# testcore.net
KiCad netlist of a schematic drawn in Altium Designer
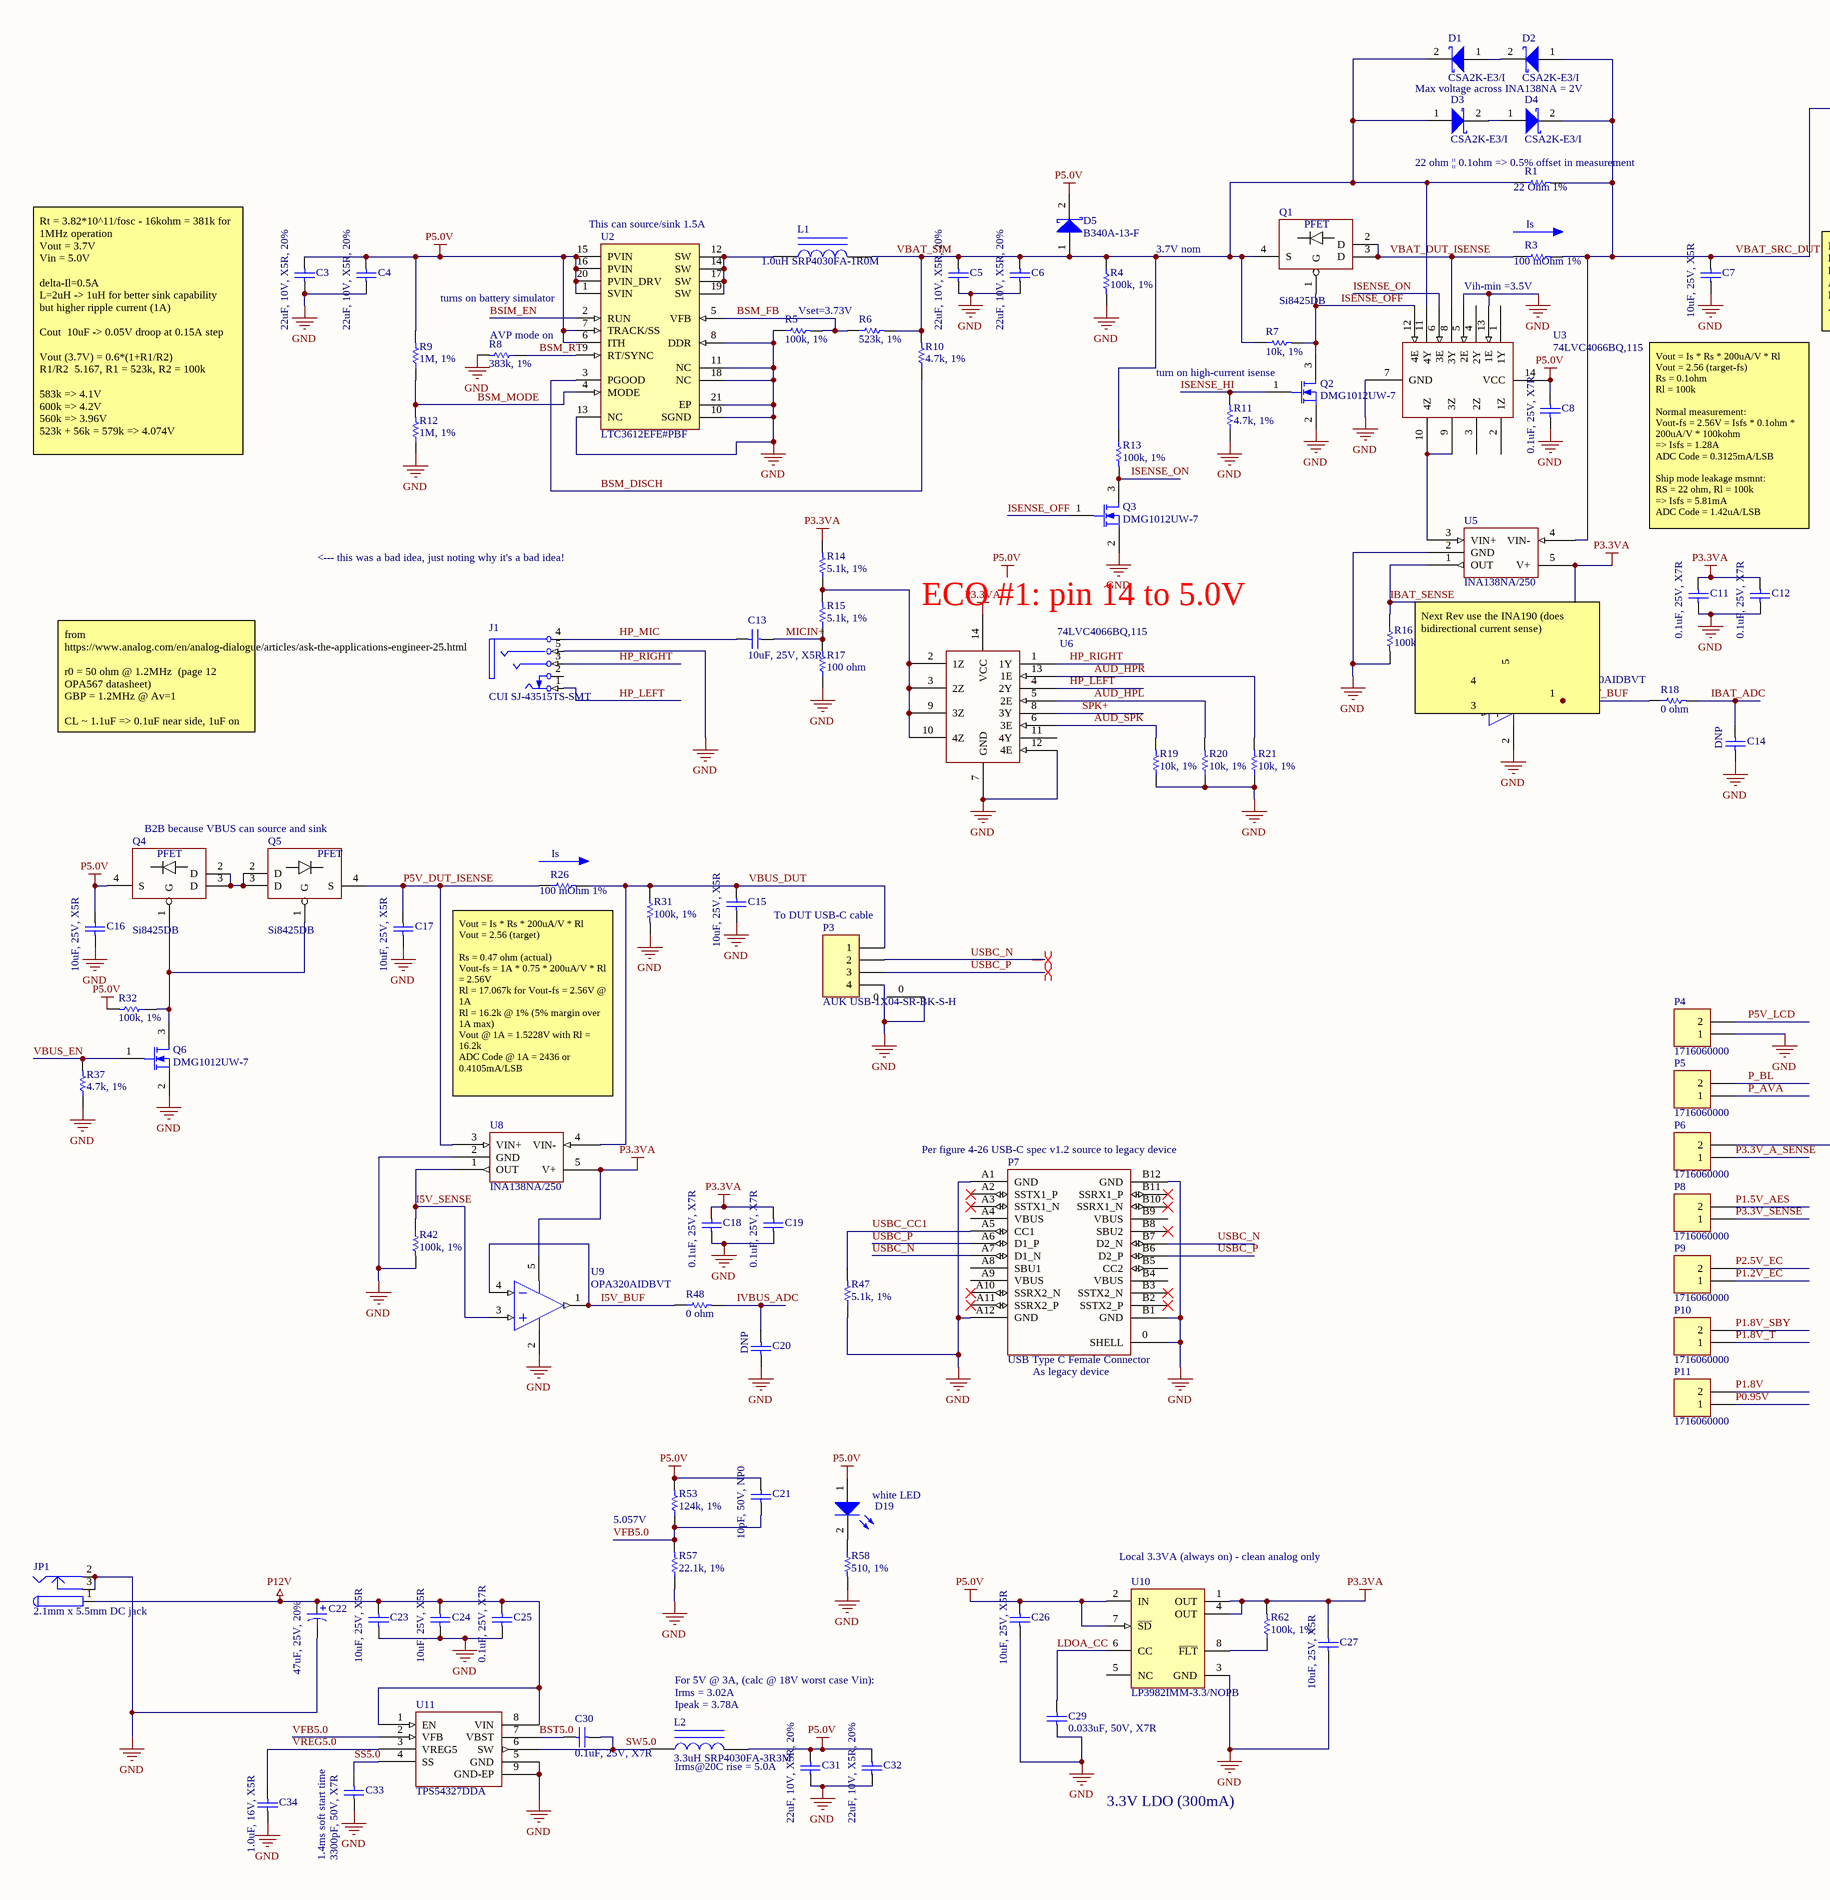
[diagram p0: testcore.SchDoc, left]
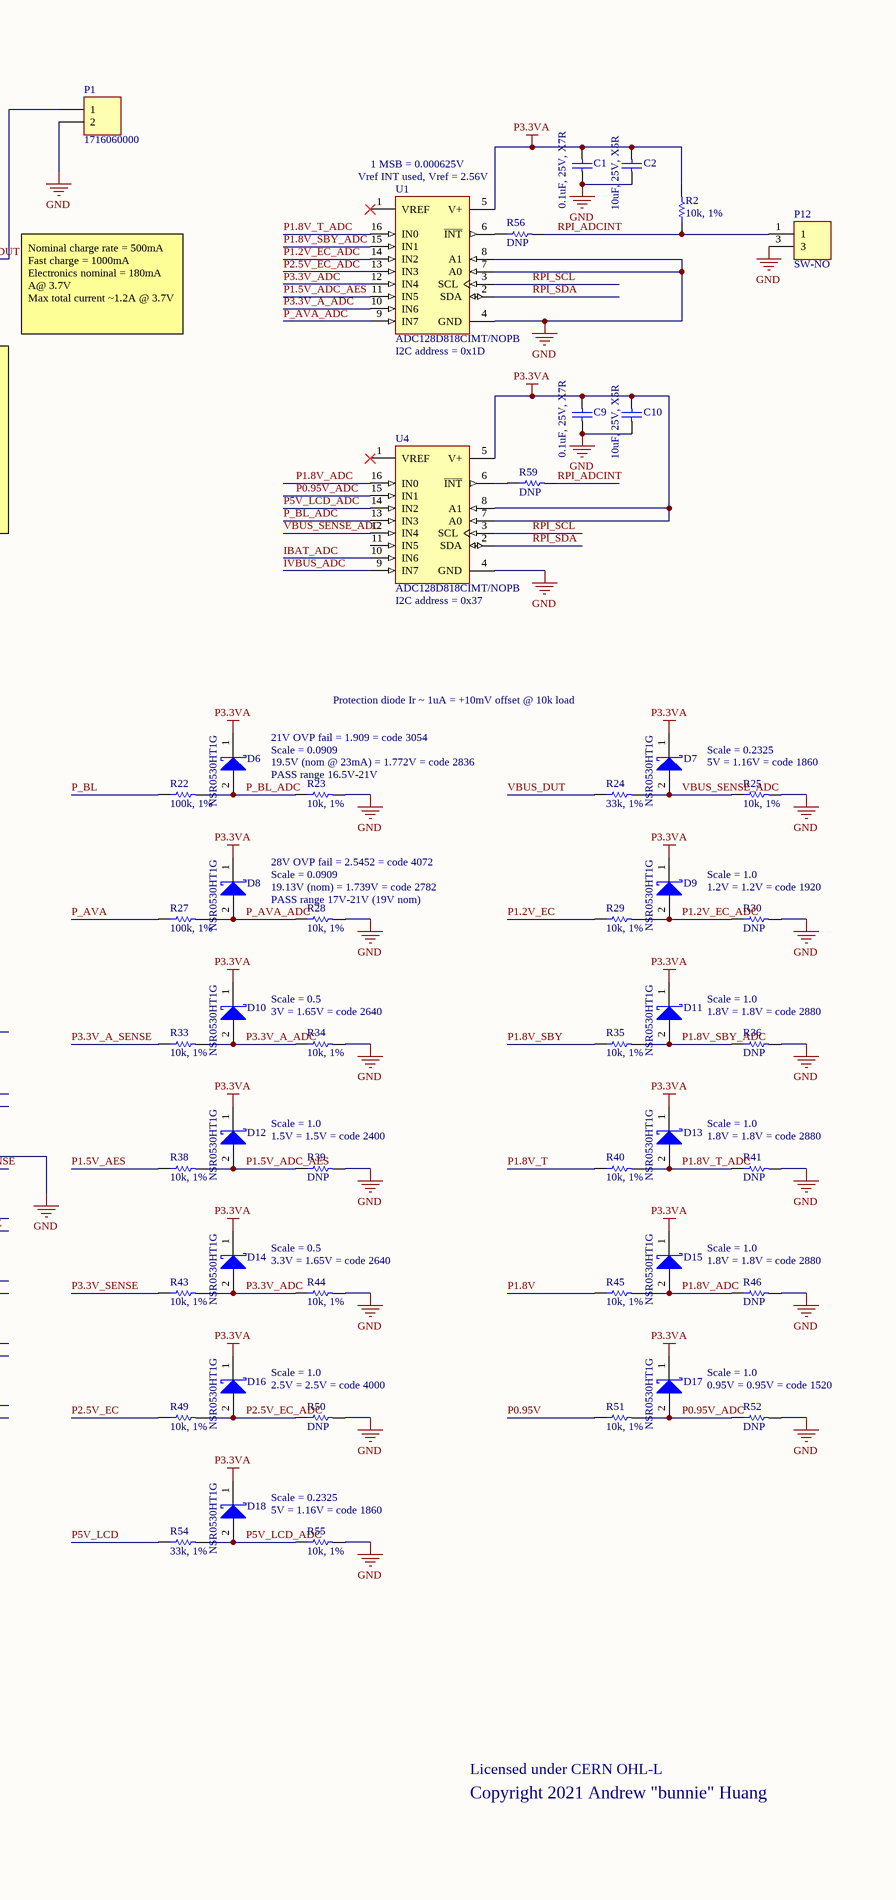
[diagram p1: testcore.SchDoc, right]

(export (version "E")
  (design (tool "Eeschema 10.0.6"))
  (components
    (comp (ref "C1")
      (value "0.1uF, 25V, X7R")
      (footprint "B_CAP0603")
      (description "Capacitor (Semiconductor SIM Model)")
      (fields (field (name "MPN") "CC0603KRX7R8BB104"))
      (libsource (lib "Miscellaneous Devices") (part "Cap Semi"))
    )
    (comp (ref "C2")
      (value "10uF, 25V, X5R")
      (footprint "B_CAP0805")
      (description "Capacitor (Semiconductor SIM Model)")
      (fields (field (name "MPN") "GRM21BR61E106KA73L"))
      (libsource (lib "Miscellaneous Devices") (part "Cap Semi"))
    )
    (comp (ref "C3")
      (value "22uF, 10V, X5R, 20%")
      (footprint "B_CAP0805")
      (description "Capacitor (Semiconductor SIM Model)")
      (fields
        (field (name "MFG") "Murata")
        (field (name "MPN") "GRM21BR61A226ME51L")
        (field (name "PUBLISHER") "Altium Limited")
      )
      (libsource (lib "Miscellaneous Devices") (part "Cap Semi"))
    )
    (comp (ref "C4")
      (value "22uF, 10V, X5R, 20%")
      (footprint "B_CAP0805")
      (description "Capacitor (Semiconductor SIM Model)")
      (fields
        (field (name "MFG") "Murata")
        (field (name "MPN") "GRM21BR61A226ME51L")
        (field (name "PUBLISHER") "Altium Limited")
      )
      (libsource (lib "Miscellaneous Devices") (part "Cap Semi"))
    )
    (comp (ref "C5")
      (value "22uF, 10V, X5R, 20%")
      (footprint "B_CAP0805")
      (description "Capacitor (Semiconductor SIM Model)")
      (fields
        (field (name "MFG") "Murata")
        (field (name "MPN") "GRM21BR61A226ME51L")
        (field (name "PUBLISHER") "Altium Limited")
      )
      (libsource (lib "Miscellaneous Devices") (part "Cap Semi"))
    )
    (comp (ref "C6")
      (value "22uF, 10V, X5R, 20%")
      (footprint "B_CAP0805")
      (description "Capacitor (Semiconductor SIM Model)")
      (fields
        (field (name "MFG") "Murata")
        (field (name "MPN") "GRM21BR61A226ME51L")
        (field (name "PUBLISHER") "Altium Limited")
      )
      (libsource (lib "Miscellaneous Devices") (part "Cap Semi"))
    )
    (comp (ref "C7")
      (value "10uF, 25V, X5R")
      (footprint "B_CAP0805")
      (description "Capacitor (Semiconductor SIM Model)")
      (fields (field (name "MPN") "GRM21BR61E106KA73L"))
      (libsource (lib "Miscellaneous Devices") (part "Cap Semi"))
    )
    (comp (ref "C8")
      (value "0.1uF, 25V, X7R")
      (footprint "B_CAP0603")
      (description "Capacitor (Semiconductor SIM Model)")
      (fields (field (name "MPN") "CC0603KRX7R8BB104"))
      (libsource (lib "Miscellaneous Devices") (part "Cap Semi"))
    )
    (comp (ref "C9")
      (value "0.1uF, 25V, X7R")
      (footprint "B_CAP0603")
      (description "Capacitor (Semiconductor SIM Model)")
      (fields (field (name "MPN") "CC0603KRX7R8BB104"))
      (libsource (lib "Miscellaneous Devices") (part "Cap Semi"))
    )
    (comp (ref "C10")
      (value "10uF, 25V, X5R")
      (footprint "B_CAP0805")
      (description "Capacitor (Semiconductor SIM Model)")
      (fields (field (name "MPN") "GRM21BR61E106KA73L"))
      (libsource (lib "Miscellaneous Devices") (part "Cap Semi"))
    )
    (comp (ref "C11")
      (value "0.1uF, 25V, X7R")
      (footprint "B_CAP0603")
      (description "Capacitor (Semiconductor SIM Model)")
      (fields (field (name "MPN") "CC0603KRX7R8BB104"))
      (libsource (lib "Miscellaneous Devices") (part "Cap Semi"))
    )
    (comp (ref "C12")
      (value "0.1uF, 25V, X7R")
      (footprint "B_CAP0603")
      (description "Capacitor (Semiconductor SIM Model)")
      (fields (field (name "MPN") "CC0603KRX7R8BB104"))
      (libsource (lib "Miscellaneous Devices") (part "Cap Semi"))
    )
    (comp (ref "C13")
      (value "10uF, 25V, X5R")
      (footprint "B_CAP0805")
      (description "Capacitor (Semiconductor SIM Model)")
      (fields (field (name "MPN") "GRM21BR61E106KA73L"))
      (libsource (lib "Miscellaneous Devices") (part "Cap Semi"))
    )
    (comp (ref "C14")
      (value "DNP")
      (footprint "B_CAP0603")
      (description "Capacitor (Semiconductor SIM Model)")
      (libsource (lib "Miscellaneous Devices") (part "Cap Semi"))
    )
    (comp (ref "C15")
      (value "10uF, 25V, X5R")
      (footprint "B_CAP0805")
      (description "Capacitor (Semiconductor SIM Model)")
      (fields (field (name "MPN") "GRM21BR61E106KA73L"))
      (libsource (lib "Miscellaneous Devices") (part "Cap Semi"))
    )
    (comp (ref "C16")
      (value "10uF, 25V, X5R")
      (footprint "B_CAP0805")
      (description "Capacitor (Semiconductor SIM Model)")
      (fields (field (name "MPN") "GRM21BR61E106KA73L"))
      (libsource (lib "Miscellaneous Devices") (part "Cap Semi"))
    )
    (comp (ref "C17")
      (value "10uF, 25V, X5R")
      (footprint "B_CAP0805")
      (description "Capacitor (Semiconductor SIM Model)")
      (fields (field (name "MPN") "GRM21BR61E106KA73L"))
      (libsource (lib "Miscellaneous Devices") (part "Cap Semi"))
    )
    (comp (ref "C18")
      (value "0.1uF, 25V, X7R")
      (footprint "B_CAP0603")
      (description "Capacitor (Semiconductor SIM Model)")
      (fields (field (name "MPN") "CC0603KRX7R8BB104"))
      (libsource (lib "Miscellaneous Devices") (part "Cap Semi"))
    )
    (comp (ref "C19")
      (value "0.1uF, 25V, X7R")
      (footprint "B_CAP0603")
      (description "Capacitor (Semiconductor SIM Model)")
      (fields (field (name "MPN") "CC0603KRX7R8BB104"))
      (libsource (lib "Miscellaneous Devices") (part "Cap Semi"))
    )
    (comp (ref "C20")
      (value "DNP")
      (footprint "B_CAP0603")
      (description "Capacitor (Semiconductor SIM Model)")
      (libsource (lib "Miscellaneous Devices") (part "Cap Semi"))
    )
    (comp (ref "C21")
      (value "10pF, 50V, NP0")
      (footprint "B_CAP0603")
      (description "Capacitor (Semiconductor SIM Model)")
      (fields (field (name "MPN") "CL10C100JB8NFNC"))
      (libsource (lib "Miscellaneous Devices") (part "Cap Semi"))
    )
    (comp (ref "C22")
      (value "47uF, 25V, 20%")
      (footprint "CAPAE7066X61N")
      (description "Polarized Capacitor (Radial)")
      (fields (field (name "MPN") "UCL1E470MCL1GS"))
      (libsource (lib "Miscellaneous Devices") (part "Cap Pol1"))
    )
    (comp (ref "C23")
      (value "10uF, 25V, X5R")
      (footprint "B_CAP0805")
      (description "Capacitor (Semiconductor SIM Model)")
      (fields (field (name "MPN") "GRM21BR61E106KA73L"))
      (libsource (lib "Miscellaneous Devices") (part "Cap Semi"))
    )
    (comp (ref "C24")
      (value "10uF, 25V, X5R")
      (footprint "B_CAP0805")
      (description "Capacitor (Semiconductor SIM Model)")
      (fields (field (name "MPN") "GRM21BR61E106KA73L"))
      (libsource (lib "Miscellaneous Devices") (part "Cap Semi"))
    )
    (comp (ref "C25")
      (value "0.1uF, 25V, X7R")
      (footprint "B_CAP0603")
      (description "Capacitor (Semiconductor SIM Model)")
      (fields (field (name "MPN") "CC0603KRX7R8BB104"))
      (libsource (lib "Miscellaneous Devices") (part "Cap Semi"))
    )
    (comp (ref "C26")
      (value "10uF, 25V, X5R")
      (footprint "B_CAP0805")
      (description "Capacitor (Semiconductor SIM Model)")
      (fields (field (name "MPN") "GRM21BR61E106KA73L"))
      (libsource (lib "Miscellaneous Devices") (part "Cap Semi"))
    )
    (comp (ref "C27")
      (value "10uF, 25V, X5R")
      (footprint "B_CAP0805")
      (description "Capacitor (Semiconductor SIM Model)")
      (fields (field (name "MPN") "GRM21BR61E106KA73L"))
      (libsource (lib "Miscellaneous Devices") (part "Cap Semi"))
    )
    (comp (ref "C29")
      (value "0.033uF, 50V, X7R")
      (footprint "B_CAP0603")
      (description "Capacitor (Semiconductor SIM Model)")
      (fields (field (name "MPN") "CL10B333KB8NNNC"))
      (libsource (lib "Miscellaneous Devices") (part "Cap Semi"))
    )
    (comp (ref "C30")
      (value "0.1uF, 25V, X7R")
      (footprint "B_CAP0603")
      (description "Capacitor (Semiconductor SIM Model)")
      (fields (field (name "MPN") "CC0603KRX7R8BB104"))
      (libsource (lib "Miscellaneous Devices") (part "Cap Semi"))
    )
    (comp (ref "C31")
      (value "22uF, 10V, X5R, 20%")
      (footprint "B_CAP0805")
      (description "Capacitor (Semiconductor SIM Model)")
      (fields
        (field (name "MFG") "Murata")
        (field (name "MPN") "GRM21BR61A226ME51L")
        (field (name "PUBLISHER") "Altium Limited")
      )
      (libsource (lib "Miscellaneous Devices") (part "Cap Semi"))
    )
    (comp (ref "C32")
      (value "22uF, 10V, X5R, 20%")
      (footprint "B_CAP0805")
      (description "Capacitor (Semiconductor SIM Model)")
      (fields
        (field (name "MFG") "Murata")
        (field (name "MPN") "GRM21BR61A226ME51L")
        (field (name "PUBLISHER") "Altium Limited")
      )
      (libsource (lib "Miscellaneous Devices") (part "Cap Semi"))
    )
    (comp (ref "C33")
      (value "3300pF, 50V, X7R")
      (footprint "B_CAP0603")
      (description "Capacitor (Semiconductor SIM Model)")
      (fields (field (name "MPN") "CL10B332KB8NNNC"))
      (libsource (lib "Miscellaneous Devices") (part "Cap Semi"))
    )
    (comp (ref "C34")
      (value "1.0uF, 16V, X5R")
      (footprint "B_CAP0603")
      (description "Capacitor (Semiconductor SIM Model)")
      (fields (field (name "MPN") "CL10B105MO8NNWC"))
      (libsource (lib "Miscellaneous Devices") (part "Cap Semi"))
    )
    (comp (ref "D1")
      (value "CSA2K-E3/I")
      (footprint "DSO-C2/X1.8")
      (description "Schottky Diode")
      (libsource (lib "") (part "D Schottky_1"))
    )
    (comp (ref "D2")
      (value "CSA2K-E3/I")
      (footprint "DSO-C2/X1.8")
      (description "Schottky Diode")
      (libsource (lib "") (part "D Schottky_1"))
    )
    (comp (ref "D3")
      (value "CSA2K-E3/I")
      (footprint "DSO-C2/X1.8")
      (description "Schottky Diode")
      (libsource (lib "") (part "D Schottky_1"))
    )
    (comp (ref "D4")
      (value "CSA2K-E3/I")
      (footprint "DSO-C2/X1.8")
      (description "Schottky Diode")
      (libsource (lib "") (part "D Schottky_1"))
    )
    (comp (ref "D5")
      (value "B340A-13-F")
      (footprint "DSO-C2/X1.8")
      (description "Schottky Diode")
      (libsource (lib "") (part "D Schottky_1"))
    )
    (comp (ref "D6")
      (value "NSR0530HT1G")
      (footprint "SOD-323")
      (description "Schottky Diode")
      (fields (field (name "MPN") "NSR0530H-D"))
      (libsource (lib "Miscellaneous Devices") (part "D Schottky"))
    )
    (comp (ref "D7")
      (value "NSR0530HT1G")
      (footprint "SOD-323")
      (description "Schottky Diode")
      (fields (field (name "MPN") "NSR0530H-D"))
      (libsource (lib "Miscellaneous Devices") (part "D Schottky"))
    )
    (comp (ref "D8")
      (value "NSR0530HT1G")
      (footprint "SOD-323")
      (description "Schottky Diode")
      (fields (field (name "MPN") "NSR0530H-D"))
      (libsource (lib "Miscellaneous Devices") (part "D Schottky"))
    )
    (comp (ref "D9")
      (value "NSR0530HT1G")
      (footprint "SOD-323")
      (description "Schottky Diode")
      (fields (field (name "MPN") "NSR0530H-D"))
      (libsource (lib "Miscellaneous Devices") (part "D Schottky"))
    )
    (comp (ref "D10")
      (value "NSR0530HT1G")
      (footprint "SOD-323")
      (description "Schottky Diode")
      (fields (field (name "MPN") "NSR0530H-D"))
      (libsource (lib "Miscellaneous Devices") (part "D Schottky"))
    )
    (comp (ref "D11")
      (value "NSR0530HT1G")
      (footprint "SOD-323")
      (description "Schottky Diode")
      (fields (field (name "MPN") "NSR0530H-D"))
      (libsource (lib "Miscellaneous Devices") (part "D Schottky"))
    )
    (comp (ref "D12")
      (value "NSR0530HT1G")
      (footprint "SOD-323")
      (description "Schottky Diode")
      (fields (field (name "MPN") "NSR0530H-D"))
      (libsource (lib "Miscellaneous Devices") (part "D Schottky"))
    )
    (comp (ref "D13")
      (value "NSR0530HT1G")
      (footprint "SOD-323")
      (description "Schottky Diode")
      (fields (field (name "MPN") "NSR0530H-D"))
      (libsource (lib "Miscellaneous Devices") (part "D Schottky"))
    )
    (comp (ref "D14")
      (value "NSR0530HT1G")
      (footprint "SOD-323")
      (description "Schottky Diode")
      (fields (field (name "MPN") "NSR0530H-D"))
      (libsource (lib "Miscellaneous Devices") (part "D Schottky"))
    )
    (comp (ref "D15")
      (value "NSR0530HT1G")
      (footprint "SOD-323")
      (description "Schottky Diode")
      (fields (field (name "MPN") "NSR0530H-D"))
      (libsource (lib "Miscellaneous Devices") (part "D Schottky"))
    )
    (comp (ref "D16")
      (value "NSR0530HT1G")
      (footprint "SOD-323")
      (description "Schottky Diode")
      (fields (field (name "MPN") "NSR0530H-D"))
      (libsource (lib "Miscellaneous Devices") (part "D Schottky"))
    )
    (comp (ref "D17")
      (value "NSR0530HT1G")
      (footprint "SOD-323")
      (description "Schottky Diode")
      (fields (field (name "MPN") "NSR0530H-D"))
      (libsource (lib "Miscellaneous Devices") (part "D Schottky"))
    )
    (comp (ref "D18")
      (value "NSR0530HT1G")
      (footprint "SOD-323")
      (description "Schottky Diode")
      (fields (field (name "MPN") "NSR0530H-D"))
      (libsource (lib "Miscellaneous Devices") (part "D Schottky"))
    )
    (comp (ref "D19")
      (value "white LED")
      (footprint "B_LED0805")
      (description "Typical RED, GREEN, YELLOW, AMBER GaAs LED")
      (fields (field (name "MPN") "IN-S85AT5UW"))
      (libsource (lib "Miscellaneous Devices") (part "LED2"))
    )
    (comp (ref "J1")
      (value "CUI SJ-43515TS-SMT")
      (footprint "CUI_SJ_43515TS-SMT")
      (description "Jack Socket, 3.5mm, SMT, 4-conductor")
      (fields (field (name "MPN") "SJ-43515TS-SMT") (field (name "PUBLISHER") "Altium Limited"))
      (libsource (lib "commonsch") (part "Phonejack4 TN"))
    )
    (comp (ref "JP1")
      (value "2.1mm x 5.5mm DC jack")
      (footprint "CUI_PJ_002AH_SMT")
      (description "Low Voltage Power Supply Connector")
      (fields (field (name "MPN") "DC-480-2.0A-SMT") (field (name "PUBLISHER") "Altium Limited"))
      (libsource (lib "Miscellaneous Connectors") (part "PWR2.5"))
    )
    (comp (ref "L1")
      (value "1.0uH SRP4030FA-1R0M")
      (footprint "COILCRAFT_XEL4030")
      (description "Magnetic-Core Inductor")
      (fields (field (name "MPN") "SRP4030FA-1R0M"))
      (libsource (lib "Miscellaneous Devices") (part "Inductor Iron"))
    )
    (comp (ref "L2")
      (value "3.3uH SRP4030FA-3R3M")
      (footprint "COILCRAFT_XEL4030")
      (description "Magnetic-Core Inductor")
      (fields (field (name "MPN") "XEL4030-332ME_"))
      (libsource (lib "Miscellaneous Devices") (part "Inductor Iron"))
    )
    (comp (ref "P1")
      (value "1716060000")
      (footprint "weidmuller_1716060000")
      (description "Header, 2-Pin")
      (fields (field (name "PUBLISHER") "Altium Limited"))
      (libsource (lib "") (part "Header 2_2"))
    )
    (comp (ref "P3")
      (value "AUK USB-1X04-SR-BK-S-H")
      (footprint "USB_TYPEA_TH_SINGLE")
      (description "Header, 4-Pin")
      (fields (field (name "PUBLISHER") "Altium Limited"))
      (libsource (lib "Miscellaneous Connectors") (part "Header 4"))
    )
    (comp (ref "P4")
      (value "1716060000")
      (footprint "weidmuller_1716060000")
      (description "Header, 2-Pin")
      (fields (field (name "PUBLISHER") "Altium Limited"))
      (libsource (lib "Miscellaneous Connectors") (part "Header 2"))
    )
    (comp (ref "P5")
      (value "1716060000")
      (footprint "weidmuller_1716060000")
      (description "Header, 2-Pin")
      (fields (field (name "PUBLISHER") "Altium Limited"))
      (libsource (lib "Miscellaneous Connectors") (part "Header 2"))
    )
    (comp (ref "P6")
      (value "1716060000")
      (footprint "weidmuller_1716060000")
      (description "Header, 2-Pin")
      (fields (field (name "PUBLISHER") "Altium Limited"))
      (libsource (lib "Miscellaneous Connectors") (part "Header 2"))
    )
    (comp (ref "P7")
      (value "USB Type C Female Connector")
      (footprint "HIROSE_CX90B1-24P")
      (description "USB Type C Connector")
      (fields (field (name "MPN") "1-2295018-2"))
      (libsource (lib "commonsch-new") (part "USB_TYPE_C"))
    )
    (comp (ref "P8")
      (value "1716060000")
      (footprint "weidmuller_1716060000")
      (description "Header, 2-Pin")
      (fields (field (name "PUBLISHER") "Altium Limited"))
      (libsource (lib "Miscellaneous Connectors") (part "Header 2"))
    )
    (comp (ref "P9")
      (value "1716060000")
      (footprint "weidmuller_1716060000")
      (description "Header, 2-Pin")
      (fields (field (name "PUBLISHER") "Altium Limited"))
      (libsource (lib "Miscellaneous Connectors") (part "Header 2"))
    )
    (comp (ref "P10")
      (value "1716060000")
      (footprint "weidmuller_1716060000")
      (description "Header, 2-Pin")
      (fields (field (name "PUBLISHER") "Altium Limited"))
      (libsource (lib "Miscellaneous Connectors") (part "Header 2"))
    )
    (comp (ref "P11")
      (value "1716060000")
      (footprint "weidmuller_1716060000")
      (description "Header, 2-Pin")
      (fields (field (name "PUBLISHER") "Altium Limited"))
      (libsource (lib "Miscellaneous Connectors") (part "Header 2"))
    )
    (comp (ref "P12")
      (value "SW-NO")
      (footprint "CK_KS11R22CQD")
      (description "Header, 2-Pin")
      (fields (field (name "PUBLISHER") "Altium Limited"))
      (libsource (lib "") (part "Header 2_1"))
    )
    (comp (ref "Q1")
      (value "Si8425DB")
      (footprint "VISHAY_MICRO_FOOT_4_BUMP")
      (description "P-channel 20V 6.2A 27mOhm @ -2.5V")
      (fields (field (name "MPN") "Si8425DB-T1-E1"))
      (libsource (lib "") (part "Si8425DB_1"))
    )
    (comp (ref "Q2")
      (value "DMG1012UW-7")
      (footprint "SOT323-3AN")
      (description "N-Channel MOSFET")
      (fields (field (name "PUBLISHER") "Altium Limited"))
      (libsource (lib "Miscellaneous Devices") (part "MOSFET-N"))
    )
    (comp (ref "Q3")
      (value "DMG1012UW-7")
      (footprint "SOT323-3AN")
      (description "N-Channel MOSFET")
      (fields (field (name "PUBLISHER") "Altium Limited"))
      (libsource (lib "Miscellaneous Devices") (part "MOSFET-N"))
    )
    (comp (ref "Q4")
      (value "Si8425DB")
      (footprint "VISHAY_MICRO_FOOT_4_BUMP")
      (description "P-channel 20V 6.2A 27mOhm @ -2.5V")
      (fields (field (name "MPN") "Si8425DB-T1-E1"))
      (libsource (lib "") (part "Si8425DB_1"))
    )
    (comp (ref "Q5")
      (value "Si8425DB")
      (footprint "VISHAY_MICRO_FOOT_4_BUMP")
      (description "P-channel 20V 6.2A 27mOhm @ -2.5V")
      (fields (field (name "MPN") "Si8425DB-T1-E1"))
      (libsource (lib "temp-to-merge") (part "Si8425DB"))
    )
    (comp (ref "Q6")
      (value "DMG1012UW-7")
      (footprint "SOT323-3AN")
      (description "N-Channel MOSFET")
      (fields (field (name "PUBLISHER") "Altium Limited"))
      (libsource (lib "Miscellaneous Devices") (part "MOSFET-N"))
    )
    (comp (ref "R1")
      (value "22 Ohm 1%")
      (footprint "B_RES1206")
      (description "Resistor")
      (fields (field (name "MPN") "ERJ-8ENF22R0V"))
      (libsource (lib "Miscellaneous Devices") (part "Res1"))
    )
    (comp (ref "R2")
      (value "10k, 1%")
      (footprint "B_RES0603")
      (description "Resistor")
      (fields (field (name "MPN") "RC0603FR-0710KL"))
      (libsource (lib "Miscellaneous Devices") (part "Res1"))
    )
    (comp (ref "R3")
      (value "100 mOhm 1%")
      (footprint "B_RES1206")
      (description "Resistor")
      (fields (field (name "MPN") "CSR1206FTR100"))
      (libsource (lib "Miscellaneous Devices") (part "Res1"))
    )
    (comp (ref "R4")
      (value "100k, 1%")
      (footprint "B_RES0603")
      (description "Resistor")
      (fields (field (name "MPN") "RC0603FR-07100KL"))
      (libsource (lib "Miscellaneous Devices") (part "Res1"))
    )
    (comp (ref "R5")
      (value "100k, 1%")
      (footprint "B_RES0603")
      (description "Resistor")
      (fields (field (name "MPN") "RC0603FR-07100KL"))
      (libsource (lib "Miscellaneous Devices") (part "Res1"))
    )
    (comp (ref "R6")
      (value "523k, 1%")
      (footprint "B_RES0603")
      (description "Resistor")
      (fields (field (name "MPN") "RC0603FR-07523KL"))
      (libsource (lib "Miscellaneous Devices") (part "Res1"))
    )
    (comp (ref "R7")
      (value "10k, 1%")
      (footprint "B_RES0603")
      (description "Resistor")
      (fields (field (name "MPN") "RC0603FR-0710KL"))
      (libsource (lib "Miscellaneous Devices") (part "Res1"))
    )
    (comp (ref "R8")
      (value "383k, 1%")
      (footprint "B_RES0603")
      (description "Resistor")
      (fields (field (name "MPN") "RC0603FR-07383KL"))
      (libsource (lib "Miscellaneous Devices") (part "Res1"))
    )
    (comp (ref "R9")
      (value "1M, 1%")
      (footprint "B_RES0603")
      (description "Resistor")
      (fields (field (name "MPN") "RC0603FR-071ML"))
      (libsource (lib "Miscellaneous Devices") (part "Res1"))
    )
    (comp (ref "R10")
      (value "4.7k, 1%")
      (footprint "B_RES0603")
      (description "Resistor")
      (fields (field (name "MPN") "RC0603FR-074K7L"))
      (libsource (lib "Miscellaneous Devices") (part "Res1"))
    )
    (comp (ref "R11")
      (value "4.7k, 1%")
      (footprint "B_RES0603")
      (description "Resistor")
      (fields (field (name "MPN") "RC0603FR-074K7L"))
      (libsource (lib "Miscellaneous Devices") (part "Res1"))
    )
    (comp (ref "R12")
      (value "1M, 1%")
      (footprint "B_RES0603")
      (description "Resistor")
      (fields (field (name "MPN") "RC0603FR-071ML"))
      (libsource (lib "Miscellaneous Devices") (part "Res1"))
    )
    (comp (ref "R13")
      (value "100k, 1%")
      (footprint "B_RES0603")
      (description "Resistor")
      (fields (field (name "MPN") "RC0603FR-07100KL"))
      (libsource (lib "Miscellaneous Devices") (part "Res1"))
    )
    (comp (ref "R14")
      (value "5.1k, 1%")
      (footprint "B_RES0603")
      (description "Resistor")
      (fields (field (name "MPN") "RC0603FR-075K1L"))
      (libsource (lib "Miscellaneous Devices") (part "Res1"))
    )
    (comp (ref "R15")
      (value "5.1k, 1%")
      (footprint "B_RES0603")
      (description "Resistor")
      (fields (field (name "MPN") "RC0603FR-075K1L"))
      (libsource (lib "Miscellaneous Devices") (part "Res1"))
    )
    (comp (ref "R16")
      (value "100k, 1%")
      (footprint "B_RES0603")
      (description "Resistor")
      (fields (field (name "MPN") "RC0603FR-07100KL"))
      (libsource (lib "Miscellaneous Devices") (part "Res1"))
    )
    (comp (ref "R17")
      (value "100 ohm")
      (footprint "B_RES0603")
      (description "Resistor")
      (fields (field (name "MPN") "RC0603FR-07100RL"))
      (libsource (lib "Miscellaneous Devices") (part "Res1"))
    )
    (comp (ref "R18")
      (value "0 ohm")
      (footprint "B_RES0603")
      (description "Resistor")
      (fields (field (name "MPN") "RC0603JR-070RL"))
      (libsource (lib "Miscellaneous Devices") (part "Res1"))
    )
    (comp (ref "R19")
      (value "10k, 1%")
      (footprint "B_RES0603")
      (description "Resistor")
      (fields (field (name "MPN") "RC0603FR-0710KL"))
      (libsource (lib "Miscellaneous Devices") (part "Res1"))
    )
    (comp (ref "R20")
      (value "10k, 1%")
      (footprint "B_RES0603")
      (description "Resistor")
      (fields (field (name "MPN") "RC0603FR-0710KL"))
      (libsource (lib "Miscellaneous Devices") (part "Res1"))
    )
    (comp (ref "R21")
      (value "10k, 1%")
      (footprint "B_RES0603")
      (description "Resistor")
      (fields (field (name "MPN") "RC0603FR-0710KL"))
      (libsource (lib "Miscellaneous Devices") (part "Res1"))
    )
    (comp (ref "R22")
      (value "100k, 1%")
      (footprint "B_RES0603")
      (description "Resistor")
      (fields (field (name "MPN") "RC0603FR-07100KL"))
      (libsource (lib "Miscellaneous Devices") (part "Res1"))
    )
    (comp (ref "R23")
      (value "10k, 1%")
      (footprint "B_RES0603")
      (description "Resistor")
      (fields (field (name "MPN") "RC0603FR-0710KL"))
      (libsource (lib "Miscellaneous Devices") (part "Res1"))
    )
    (comp (ref "R24")
      (value "33k, 1%")
      (footprint "B_RES0603")
      (description "Resistor")
      (fields (field (name "MPN") "RC0603FR-0733KL"))
      (libsource (lib "Miscellaneous Devices") (part "Res1"))
    )
    (comp (ref "R25")
      (value "10k, 1%")
      (footprint "B_RES0603")
      (description "Resistor")
      (fields (field (name "MPN") "RC0603FR-0710KL"))
      (libsource (lib "Miscellaneous Devices") (part "Res1"))
    )
    (comp (ref "R26")
      (value "100 mOhm 1%")
      (footprint "B_RES1206")
      (description "Resistor")
      (fields (field (name "MPN") "CSR1206FTR100"))
      (libsource (lib "Miscellaneous Devices") (part "Res1"))
    )
    (comp (ref "R27")
      (value "100k, 1%")
      (footprint "B_RES0603")
      (description "Resistor")
      (fields (field (name "MPN") "RC0603FR-07100KL"))
      (libsource (lib "Miscellaneous Devices") (part "Res1"))
    )
    (comp (ref "R28")
      (value "10k, 1%")
      (footprint "B_RES0603")
      (description "Resistor")
      (fields (field (name "MPN") "RC0603FR-0710KL"))
      (libsource (lib "Miscellaneous Devices") (part "Res1"))
    )
    (comp (ref "R29")
      (value "10k, 1%")
      (footprint "B_RES0603")
      (description "Resistor")
      (fields (field (name "MPN") "RC0603FR-0710KL"))
      (libsource (lib "Miscellaneous Devices") (part "Res1"))
    )
    (comp (ref "R30")
      (value "DNP")
      (footprint "B_RES0603")
      (description "Resistor")
      (fields (field (name "MPN") "ANY"))
      (libsource (lib "Miscellaneous Devices") (part "Res1"))
    )
    (comp (ref "R31")
      (value "100k, 1%")
      (footprint "B_RES0603")
      (description "Resistor")
      (fields (field (name "MPN") "RC0603FR-07100KL"))
      (libsource (lib "Miscellaneous Devices") (part "Res1"))
    )
    (comp (ref "R32")
      (value "100k, 1%")
      (footprint "B_RES0603")
      (description "Resistor")
      (fields (field (name "MPN") "RC0603FR-07100KL"))
      (libsource (lib "Miscellaneous Devices") (part "Res1"))
    )
    (comp (ref "R33")
      (value "10k, 1%")
      (footprint "B_RES0603")
      (description "Resistor")
      (fields (field (name "MPN") "RC0603FR-0710KL"))
      (libsource (lib "Miscellaneous Devices") (part "Res1"))
    )
    (comp (ref "R34")
      (value "10k, 1%")
      (footprint "B_RES0603")
      (description "Resistor")
      (fields (field (name "MPN") "RC0603FR-0710KL"))
      (libsource (lib "Miscellaneous Devices") (part "Res1"))
    )
    (comp (ref "R35")
      (value "10k, 1%")
      (footprint "B_RES0603")
      (description "Resistor")
      (fields (field (name "MPN") "RC0603FR-0710KL"))
      (libsource (lib "Miscellaneous Devices") (part "Res1"))
    )
    (comp (ref "R36")
      (value "DNP")
      (footprint "B_RES0603")
      (description "Resistor")
      (fields (field (name "MPN") "ANY"))
      (libsource (lib "Miscellaneous Devices") (part "Res1"))
    )
    (comp (ref "R37")
      (value "4.7k, 1%")
      (footprint "B_RES0603")
      (description "Resistor")
      (fields (field (name "MPN") "RC0603FR-074K7L"))
      (libsource (lib "Miscellaneous Devices") (part "Res1"))
    )
    (comp (ref "R38")
      (value "10k, 1%")
      (footprint "B_RES0603")
      (description "Resistor")
      (fields (field (name "MPN") "RC0603FR-0710KL"))
      (libsource (lib "Miscellaneous Devices") (part "Res1"))
    )
    (comp (ref "R39")
      (value "DNP")
      (footprint "B_RES0603")
      (description "Resistor")
      (fields (field (name "MPN") "ANY"))
      (libsource (lib "Miscellaneous Devices") (part "Res1"))
    )
    (comp (ref "R40")
      (value "10k, 1%")
      (footprint "B_RES0603")
      (description "Resistor")
      (fields (field (name "MPN") "RC0603FR-0710KL"))
      (libsource (lib "Miscellaneous Devices") (part "Res1"))
    )
    (comp (ref "R41")
      (value "DNP")
      (footprint "B_RES0603")
      (description "Resistor")
      (fields (field (name "MPN") "ANY"))
      (libsource (lib "Miscellaneous Devices") (part "Res1"))
    )
    (comp (ref "R42")
      (value "100k, 1%")
      (footprint "B_RES0603")
      (description "Resistor")
      (fields (field (name "MPN") "RC0603FR-07100KL"))
      (libsource (lib "Miscellaneous Devices") (part "Res1"))
    )
    (comp (ref "R43")
      (value "10k, 1%")
      (footprint "B_RES0603")
      (description "Resistor")
      (fields (field (name "MPN") "RC0603FR-0710KL"))
      (libsource (lib "Miscellaneous Devices") (part "Res1"))
    )
    (comp (ref "R44")
      (value "10k, 1%")
      (footprint "B_RES0603")
      (description "Resistor")
      (fields (field (name "MPN") "RC0603FR-0710KL"))
      (libsource (lib "Miscellaneous Devices") (part "Res1"))
    )
    (comp (ref "R45")
      (value "10k, 1%")
      (footprint "B_RES0603")
      (description "Resistor")
      (fields (field (name "MPN") "RC0603FR-0710KL"))
      (libsource (lib "Miscellaneous Devices") (part "Res1"))
    )
    (comp (ref "R46")
      (value "DNP")
      (footprint "B_RES0603")
      (description "Resistor")
      (fields (field (name "MPN") "ANY"))
      (libsource (lib "Miscellaneous Devices") (part "Res1"))
    )
    (comp (ref "R47")
      (value "5.1k, 1%")
      (footprint "B_RES0603")
      (description "Resistor")
      (fields (field (name "MPN") "RC0603FR-075K1L"))
      (libsource (lib "Miscellaneous Devices") (part "Res1"))
    )
    (comp (ref "R48")
      (value "0 ohm")
      (footprint "B_RES0603")
      (description "Resistor")
      (fields (field (name "MPN") "RC0603JR-070RL"))
      (libsource (lib "Miscellaneous Devices") (part "Res1"))
    )
    (comp (ref "R49")
      (value "10k, 1%")
      (footprint "B_RES0603")
      (description "Resistor")
      (fields (field (name "MPN") "RC0603FR-0710KL"))
      (libsource (lib "Miscellaneous Devices") (part "Res1"))
    )
    (comp (ref "R50")
      (value "DNP")
      (footprint "B_RES0603")
      (description "Resistor")
      (fields (field (name "MPN") "ANY"))
      (libsource (lib "Miscellaneous Devices") (part "Res1"))
    )
    (comp (ref "R51")
      (value "10k, 1%")
      (footprint "B_RES0603")
      (description "Resistor")
      (fields (field (name "MPN") "RC0603FR-0710KL"))
      (libsource (lib "Miscellaneous Devices") (part "Res1"))
    )
    (comp (ref "R52")
      (value "DNP")
      (footprint "B_RES0603")
      (description "Resistor")
      (fields (field (name "MPN") "ANY"))
      (libsource (lib "Miscellaneous Devices") (part "Res1"))
    )
    (comp (ref "R53")
      (value "124k, 1%")
      (footprint "B_RES0603")
      (description "Resistor")
      (fields (field (name "MPN") "RC0603FR-07124KL"))
      (libsource (lib "Miscellaneous Devices") (part "Res1"))
    )
    (comp (ref "R54")
      (value "33k, 1%")
      (footprint "B_RES0603")
      (description "Resistor")
      (fields (field (name "MPN") "RC0603FR-0733KL"))
      (libsource (lib "Miscellaneous Devices") (part "Res1"))
    )
    (comp (ref "R55")
      (value "10k, 1%")
      (footprint "B_RES0603")
      (description "Resistor")
      (fields (field (name "MPN") "RC0603FR-0710KL"))
      (libsource (lib "Miscellaneous Devices") (part "Res1"))
    )
    (comp (ref "R56")
      (value "DNP")
      (footprint "B_RES0603")
      (description "Resistor")
      (fields (field (name "MPN") "ANY"))
      (libsource (lib "Miscellaneous Devices") (part "Res1"))
    )
    (comp (ref "R57")
      (value "22.1k, 1%")
      (footprint "B_RES0603")
      (description "Resistor")
      (fields (field (name "MPN") "RC0603FR-0722K1L"))
      (libsource (lib "Miscellaneous Devices") (part "Res1"))
    )
    (comp (ref "R58")
      (value "510, 1%")
      (footprint "B_RES0603")
      (description "Resistor")
      (fields (field (name "MPN") "RC0603FR-07510RL") (field (name "PUBLISHER") "Altium Limited"))
      (libsource (lib "Miscellaneous Devices") (part "Res1"))
    )
    (comp (ref "R59")
      (value "DNP")
      (footprint "B_RES0603")
      (description "Resistor")
      (fields (field (name "MPN") "ANY"))
      (libsource (lib "Miscellaneous Devices") (part "Res1"))
    )
    (comp (ref "R62")
      (value "100k, 1%")
      (footprint "B_RES0603")
      (description "Resistor")
      (fields (field (name "MPN") "RC0603FR-07100KL"))
      (libsource (lib "Miscellaneous Devices") (part "Res1"))
    )
    (comp (ref "U1")
      (value "ADC128D818CIMT/NOPB")
      (footprint "MTC16_N")
      (fields (field (name "MANUFACTURER") "National Semiconductor"))
      (libsource (lib "National Semiconductor ADC") (part "ADC128D818CIMT/NOPB"))
    )
    (comp (ref "U2")
      (value "LTC3612EFE#PBF")
      (footprint "LT-FE-20-EPV-CB_L")
      (libsource (lib "Altium Content Vault") (part "LT-LTC3612-FE-20"))
    )
    (comp (ref "U3")
      (value "74LVC4066BQ,115")
      (footprint "NXP_DHVQFN14")
      (description "Quad Bilateral Switch")
      (libsource (lib "commonsch-new") (part "74LVC4066"))
    )
    (comp (ref "U4")
      (value "ADC128D818CIMT/NOPB")
      (footprint "MTC16_N")
      (fields (field (name "MANUFACTURER") "National Semiconductor"))
      (libsource (lib "National Semiconductor ADC") (part "ADC128D818CIMT/NOPB"))
    )
    (comp (ref "U5")
      (value "INA138NA/250")
      (footprint "SOT23-5AN")
      (description "High-side measurement current shunt monitor")
      (libsource (lib "commonsch-new") (part "INA138NA/250"))
    )
    (comp (ref "U6")
      (value "74LVC4066BQ,115")
      (footprint "NXP_DHVQFN14")
      (description "Quad Bilateral Switch")
      (libsource (lib "commonsch-new") (part "74LVC4066"))
    )
    (comp (ref "U7")
      (value "OPA320AIDBVT")
      (footprint "TI-DBV5_N")
      (fields (field (name "MANUFACTURER") "Texas Instruments"))
      (libsource (lib "TI Amplifiers and Linear Operational Amplifier Precision Amplifier Part One") (part "OPA320AIDBVT"))
    )
    (comp (ref "U8")
      (value "INA138NA/250")
      (footprint "SOT23-5AN")
      (description "High-side measurement current shunt monitor")
      (libsource (lib "commonsch-new") (part "INA138NA/250"))
    )
    (comp (ref "U9")
      (value "OPA320AIDBVT")
      (footprint "TI-DBV5_N")
      (fields (field (name "MANUFACTURER") "Texas Instruments"))
      (libsource (lib "TI Amplifiers and Linear Operational Amplifier Precision Amplifier Part One") (part "OPA320AIDBVT"))
    )
    (comp (ref "U10")
      (value "LP3982IMM-3.3/NOPB")
      (footprint "MUA08A_N")
      (description "Micropower, Ultra Low-Dropout, Low-Noise, 300mA CMOS Regulator, 8-pin Mini SOIC, Pb-Free")
      (fields (field (name "MANUFACTURER") "National Semiconductor"))
      (libsource (lib "National Semiconductor LDO") (part "LP3982IMM-3.3/NOPB"))
    )
    (comp (ref "U11")
      (value "TPS54327DDA")
      (footprint "SOIC127P600-8DN")
      (description "3-A Output Single Synchronous Step-Down Buck with Integrated FET")
      (fields (field (name "MPN") "TPS54327DDA(R)"))
      (libsource (lib "commonsch-new") (part "TPS54327DDA"))
    )
  )
  (nets
    (net (code "1") (name "/AUD_HPL") (class "Default")
      (node (ref "R20") (pin "2") (pinfunction "2_2") (pintype "passive"))
      (node (ref "U6") (pin "5") (pinfunction "2E_5") (pintype "input"))
    )
    (net (code "2") (name "/AUD_HPR") (class "Default")
      (node (ref "R21") (pin "2") (pinfunction "2_2") (pintype "passive"))
      (node (ref "U6") (pin "13") (pinfunction "1E_13") (pintype "input"))
    )
    (net (code "3") (name "/AUD_SPK") (class "Default")
      (node (ref "R19") (pin "2") (pinfunction "2_2") (pintype "passive"))
      (node (ref "U6") (pin "6") (pinfunction "3E_6") (pintype "input"))
    )
    (net (code "4") (name "/BSIM_EN") (class "Default")
      (node (ref "U2") (pin "2") (pinfunction "RUN_2") (pintype "input"))
    )
    (net (code "5") (name "/BSM_DISCH") (class "Default")
      (node (ref "R10") (pin "1") (pinfunction "1_1") (pintype "passive"))
      (node (ref "U2") (pin "3") (pinfunction "PGOOD_3") (pintype "open_collector"))
    )
    (net (code "6") (name "/BSM_FB") (class "Default")
      (node (ref "R5") (pin "2") (pinfunction "2_2") (pintype "passive"))
      (node (ref "R6") (pin "1") (pinfunction "1_1") (pintype "passive"))
      (node (ref "U2") (pin "5") (pinfunction "VFB_5") (pintype "input"))
    )
    (net (code "7") (name "/BSM_MODE") (class "Default")
      (node (ref "R12") (pin "2") (pinfunction "2_2") (pintype "passive"))
      (node (ref "R9") (pin "1") (pinfunction "1_1") (pintype "passive"))
      (node (ref "U2") (pin "4") (pinfunction "MODE_4") (pintype "input"))
    )
    (net (code "8") (name "/BSM_RT") (class "Default")
      (node (ref "R8") (pin "1") (pinfunction "1_1") (pintype "passive"))
      (node (ref "U2") (pin "9") (pinfunction "RT/SYNC_9") (pintype "input"))
    )
    (net (code "9") (name "/BST5.0") (class "Default")
      (node (ref "C30") (pin "2") (pinfunction "2_2") (pintype "passive"))
      (node (ref "U11") (pin "7") (pinfunction "VBST_7") (pintype "passive"))
    )
    (net (code "10") (name "/HP_LEFT") (class "Default")
      (node (ref "J1") (pin "1") (pinfunction "T_1") (pintype "input"))
      (node (ref "U6") (pin "4") (pinfunction "2Y_4") (pintype "passive"))
    )
    (net (code "11") (name "/HP_MIC") (class "Default")
      (node (ref "C13") (pin "2") (pinfunction "2_2") (pintype "passive"))
      (node (ref "J1") (pin "4") (pinfunction "S_4") (pintype "power_in"))
    )
    (net (code "12") (name "/HP_RIGHT") (class "Default")
      (node (ref "J1") (pin "3") (pinfunction "R_3") (pintype "input"))
      (node (ref "U6") (pin "1") (pinfunction "1Y_1") (pintype "passive"))
    )
    (net (code "13") (name "/I5V_BUF") (class "Default")
      (node (ref "R48") (pin "1") (pinfunction "1_1") (pintype "passive"))
      (node (ref "U9") (pin "1") (pinfunction "OUT_1") (pintype "output"))
      (node (ref "U9") (pin "4") (pinfunction "IN-_4") (pintype "input"))
    )
    (net (code "14") (name "/I5V_SENSE") (class "Default")
      (node (ref "R42") (pin "1") (pinfunction "1_1") (pintype "passive"))
      (node (ref "U8") (pin "1") (pinfunction "OUT_1") (pintype "output"))
      (node (ref "U9") (pin "3") (pinfunction "IN+_3") (pintype "input"))
    )
    (net (code "15") (name "/IBAT_ADC") (class "Default")
      (node (ref "C14") (pin "1") (pinfunction "1_1") (pintype "passive"))
      (node (ref "R18") (pin "2") (pinfunction "2_2") (pintype "passive"))
      (node (ref "U4") (pin "10") (pinfunction "IN6_10") (pintype "input"))
    )
    (net (code "16") (name "/IBAT_BUF") (class "Default")
      (node (ref "R18") (pin "1") (pinfunction "1_1") (pintype "passive"))
      (node (ref "U7") (pin "1") (pinfunction "OUT_1") (pintype "output"))
      (node (ref "U7") (pin "4") (pinfunction "IN-_4") (pintype "input"))
    )
    (net (code "17") (name "/IBAT_SENSE") (class "Default")
      (node (ref "R16") (pin "1") (pinfunction "1_1") (pintype "passive"))
      (node (ref "U5") (pin "1") (pinfunction "OUT_1") (pintype "output"))
      (node (ref "U7") (pin "3") (pinfunction "IN+_3") (pintype "input"))
    )
    (net (code "18") (name "/ISENSE_HI") (class "Default")
      (node (ref "Q2") (pin "1") (pinfunction "G_1") (pintype "passive"))
      (node (ref "R11") (pin "2") (pinfunction "2_2") (pintype "passive"))
    )
    (net (code "19") (name "/ISENSE_OFF") (class "Default")
      (node (ref "Q1") (pin "1") (pinfunction "G_1") (pintype "passive"))
      (node (ref "Q2") (pin "3") (pinfunction "D_3") (pintype "passive"))
      (node (ref "Q3") (pin "1") (pinfunction "G_1") (pintype "passive"))
      (node (ref "R7") (pin "2") (pinfunction "2_2") (pintype "passive"))
      (node (ref "U3") (pin "12") (pinfunction "4E_12") (pintype "input"))
    )
    (net (code "20") (name "/ISENSE_ON") (class "Default")
      (node (ref "Q3") (pin "3") (pinfunction "D_3") (pintype "passive"))
      (node (ref "R13") (pin "2") (pinfunction "2_2") (pintype "passive"))
      (node (ref "U3") (pin "6") (pinfunction "3E_6") (pintype "input"))
    )
    (net (code "21") (name "/IVBUS_ADC") (class "Default")
      (node (ref "C20") (pin "1") (pinfunction "1_1") (pintype "passive"))
      (node (ref "R48") (pin "2") (pinfunction "2_2") (pintype "passive"))
      (node (ref "U4") (pin "9") (pinfunction "IN7_9") (pintype "input"))
    )
    (net (code "22") (name "/LDOA_CC") (class "Default")
      (node (ref "C29") (pin "2") (pinfunction "2_2") (pintype "passive"))
      (node (ref "U10") (pin "6") (pinfunction "CC_6") (pintype "passive"))
    )
    (net (code "23") (name "/MICIN+") (class "Default")
      (node (ref "C13") (pin "1") (pinfunction "1_1") (pintype "passive"))
      (node (ref "R15") (pin "1") (pinfunction "1_1") (pintype "passive"))
      (node (ref "R17") (pin "2") (pinfunction "2_2") (pintype "passive"))
    )
    (net (code "24") (name "/P0.95V") (class "Default")
      (node (ref "P11") (pin "1") (pinfunction "1_1") (pintype "passive"))
      (node (ref "R51") (pin "1") (pinfunction "1_1") (pintype "passive"))
    )
    (net (code "25") (name "/P0.95V_ADC") (class "Default")
      (node (ref "D17") (pin "2") (pinfunction "A_2") (pintype "passive"))
      (node (ref "R51") (pin "2") (pinfunction "2_2") (pintype "passive"))
      (node (ref "R52") (pin "1") (pinfunction "1_1") (pintype "passive"))
      (node (ref "U4") (pin "15") (pinfunction "IN1_15") (pintype "input"))
    )
    (net (code "26") (name "/P1.2V_EC") (class "Default")
      (node (ref "P9") (pin "1") (pinfunction "1_1") (pintype "passive"))
      (node (ref "R29") (pin "1") (pinfunction "1_1") (pintype "passive"))
    )
    (net (code "27") (name "/P1.2V_EC_ADC") (class "Default")
      (node (ref "D9") (pin "2") (pinfunction "A_2") (pintype "passive"))
      (node (ref "R29") (pin "2") (pinfunction "2_2") (pintype "passive"))
      (node (ref "R30") (pin "1") (pinfunction "1_1") (pintype "passive"))
      (node (ref "U1") (pin "14") (pinfunction "IN2_14") (pintype "input"))
    )
    (net (code "28") (name "/P1.5V_ADC_AES") (class "Default")
      (node (ref "D12") (pin "2") (pinfunction "A_2") (pintype "passive"))
      (node (ref "R38") (pin "2") (pinfunction "2_2") (pintype "passive"))
      (node (ref "R39") (pin "1") (pinfunction "1_1") (pintype "passive"))
      (node (ref "U1") (pin "11") (pinfunction "IN5_11") (pintype "input"))
    )
    (net (code "29") (name "/P1.5V_AES") (class "Default")
      (node (ref "P8") (pin "2") (pinfunction "2_2") (pintype "passive"))
      (node (ref "R38") (pin "1") (pinfunction "1_1") (pintype "passive"))
    )
    (net (code "30") (name "/P1.8V") (class "Default")
      (node (ref "P11") (pin "2") (pinfunction "2_2") (pintype "passive"))
      (node (ref "R45") (pin "1") (pinfunction "1_1") (pintype "passive"))
    )
    (net (code "31") (name "/P1.8V_ADC") (class "Default")
      (node (ref "D15") (pin "2") (pinfunction "A_2") (pintype "passive"))
      (node (ref "R45") (pin "2") (pinfunction "2_2") (pintype "passive"))
      (node (ref "R46") (pin "1") (pinfunction "1_1") (pintype "passive"))
      (node (ref "U4") (pin "16") (pinfunction "IN0_16") (pintype "input"))
    )
    (net (code "32") (name "/P1.8V_SBY") (class "Default")
      (node (ref "P10") (pin "2") (pinfunction "2_2") (pintype "passive"))
      (node (ref "R35") (pin "1") (pinfunction "1_1") (pintype "passive"))
    )
    (net (code "33") (name "/P1.8V_SBY_ADC") (class "Default")
      (node (ref "D11") (pin "2") (pinfunction "A_2") (pintype "passive"))
      (node (ref "R35") (pin "2") (pinfunction "2_2") (pintype "passive"))
      (node (ref "R36") (pin "1") (pinfunction "1_1") (pintype "passive"))
      (node (ref "U1") (pin "15") (pinfunction "IN1_15") (pintype "input"))
    )
    (net (code "34") (name "/P1.8V_T") (class "Default")
      (node (ref "P10") (pin "1") (pinfunction "1_1") (pintype "passive"))
      (node (ref "R40") (pin "1") (pinfunction "1_1") (pintype "passive"))
    )
    (net (code "35") (name "/P1.8V_T_ADC") (class "Default")
      (node (ref "D13") (pin "2") (pinfunction "A_2") (pintype "passive"))
      (node (ref "R40") (pin "2") (pinfunction "2_2") (pintype "passive"))
      (node (ref "R41") (pin "1") (pinfunction "1_1") (pintype "passive"))
      (node (ref "U1") (pin "16") (pinfunction "IN0_16") (pintype "input"))
    )
    (net (code "36") (name "/P2.5V_EC") (class "Default")
      (node (ref "P9") (pin "2") (pinfunction "2_2") (pintype "passive"))
      (node (ref "R49") (pin "1") (pinfunction "1_1") (pintype "passive"))
    )
    (net (code "37") (name "/P2.5V_EC_ADC") (class "Default")
      (node (ref "D16") (pin "2") (pinfunction "A_2") (pintype "passive"))
      (node (ref "R49") (pin "2") (pinfunction "2_2") (pintype "passive"))
      (node (ref "R50") (pin "1") (pinfunction "1_1") (pintype "passive"))
      (node (ref "U1") (pin "13") (pinfunction "IN3_13") (pintype "input"))
    )
    (net (code "38") (name "/P3.3V_ADC") (class "Default")
      (node (ref "D14") (pin "2") (pinfunction "A_2") (pintype "passive"))
      (node (ref "R43") (pin "2") (pinfunction "2_2") (pintype "passive"))
      (node (ref "R44") (pin "1") (pinfunction "1_1") (pintype "passive"))
      (node (ref "U1") (pin "12") (pinfunction "IN4_12") (pintype "input"))
    )
    (net (code "39") (name "/P3.3V_A_ADC") (class "Default")
      (node (ref "D10") (pin "2") (pinfunction "A_2") (pintype "passive"))
      (node (ref "R33") (pin "2") (pinfunction "2_2") (pintype "passive"))
      (node (ref "R34") (pin "1") (pinfunction "1_1") (pintype "passive"))
      (node (ref "U1") (pin "10") (pinfunction "IN6_10") (pintype "input"))
    )
    (net (code "40") (name "/P3.3V_A_SENSE") (class "Default")
      (node (ref "P6") (pin "1") (pinfunction "1_1") (pintype "passive"))
      (node (ref "R33") (pin "1") (pinfunction "1_1") (pintype "passive"))
    )
    (net (code "41") (name "/P3.3V_SENSE") (class "Default")
      (node (ref "P8") (pin "1") (pinfunction "1_1") (pintype "passive"))
      (node (ref "R43") (pin "1") (pinfunction "1_1") (pintype "passive"))
    )
    (net (code "42") (name "/P5V_DUT_ISENSE") (class "Default")
      (node (ref "C17") (pin "2") (pinfunction "2_2") (pintype "passive"))
      (node (ref "Q5") (pin "4") (pinfunction "S_4") (pintype "passive"))
      (node (ref "R26") (pin "1") (pinfunction "1_1") (pintype "passive"))
      (node (ref "U8") (pin "3") (pinfunction "VIN+_3") (pintype "input"))
    )
    (net (code "43") (name "/P5V_LCD") (class "Default")
      (node (ref "P4") (pin "2") (pinfunction "2_2") (pintype "passive"))
      (node (ref "R54") (pin "1") (pinfunction "1_1") (pintype "passive"))
    )
    (net (code "44") (name "/P5V_LCD_ADC") (class "Default")
      (node (ref "D18") (pin "2") (pinfunction "A_2") (pintype "passive"))
      (node (ref "R54") (pin "2") (pinfunction "2_2") (pintype "passive"))
      (node (ref "R55") (pin "1") (pinfunction "1_1") (pintype "passive"))
      (node (ref "U4") (pin "14") (pinfunction "IN2_14") (pintype "input"))
    )
    (net (code "45") (name "/P_AVA") (class "Default")
      (node (ref "P5") (pin "1") (pinfunction "1_1") (pintype "passive"))
      (node (ref "R27") (pin "1") (pinfunction "1_1") (pintype "passive"))
    )
    (net (code "46") (name "/P_AVA_ADC") (class "Default")
      (node (ref "D8") (pin "2") (pinfunction "A_2") (pintype "passive"))
      (node (ref "R27") (pin "2") (pinfunction "2_2") (pintype "passive"))
      (node (ref "R28") (pin "1") (pinfunction "1_1") (pintype "passive"))
      (node (ref "U1") (pin "9") (pinfunction "IN7_9") (pintype "input"))
    )
    (net (code "47") (name "/P_BL") (class "Default")
      (node (ref "P5") (pin "2") (pinfunction "2_2") (pintype "passive"))
      (node (ref "R22") (pin "1") (pinfunction "1_1") (pintype "passive"))
    )
    (net (code "48") (name "/P_BL_ADC") (class "Default")
      (node (ref "D6") (pin "2") (pinfunction "A_2") (pintype "passive"))
      (node (ref "R22") (pin "2") (pinfunction "2_2") (pintype "passive"))
      (node (ref "R23") (pin "1") (pinfunction "1_1") (pintype "passive"))
      (node (ref "U4") (pin "13") (pinfunction "IN3_13") (pintype "input"))
    )
    (net (code "49") (name "/RPI_ADCINT") (class "Default")
      (node (ref "P12") (pin "1") (pinfunction "1_1") (pintype "passive"))
      (node (ref "R2") (pin "1") (pinfunction "1_1") (pintype "passive"))
      (node (ref "R56") (pin "2") (pinfunction "2_2") (pintype "passive"))
      (node (ref "R59") (pin "2") (pinfunction "2_2") (pintype "passive"))
    )
    (net (code "50") (name "/RPI_SCL") (class "Default")
      (node (ref "U1") (pin "3") (pinfunction "SCL_3") (pintype "input"))
      (node (ref "U4") (pin "3") (pinfunction "SCL_3") (pintype "input"))
    )
    (net (code "51") (name "/RPI_SDA") (class "Default")
      (node (ref "U1") (pin "2") (pinfunction "SDA_2") (pintype "bidirectional"))
      (node (ref "U4") (pin "2") (pinfunction "SDA_2") (pintype "bidirectional"))
    )
    (net (code "52") (name "/SPK+") (class "Default")
      (node (ref "U6") (pin "8") (pinfunction "3Y_8") (pintype "passive"))
    )
    (net (code "53") (name "/SS5.0") (class "Default")
      (node (ref "C33") (pin "1") (pinfunction "1_1") (pintype "passive"))
      (node (ref "U11") (pin "4") (pinfunction "SS_4") (pintype "passive"))
    )
    (net (code "54") (name "/SW5.0") (class "Default")
      (node (ref "C30") (pin "1") (pinfunction "1_1") (pintype "passive"))
      (node (ref "L2") (pin "1") (pinfunction "1_1") (pintype "passive"))
      (node (ref "U11") (pin "6") (pinfunction "SW_6") (pintype "output"))
    )
    (net (code "55") (name "/USBC_CC1") (class "Default")
      (node (ref "P7") (pin "A5") (pinfunction "CC1_A5") (pintype "bidirectional"))
      (node (ref "R47") (pin "2") (pinfunction "2_2") (pintype "passive"))
    )
    (net (code "56") (name "/USBC_N") (class "Default")
      (node (ref "P3") (pin "2") (pinfunction "2_2") (pintype "passive"))
      (node (ref "P7") (pin "A7") (pinfunction "D1_N_A7") (pintype "bidirectional"))
      (node (ref "P7") (pin "B7") (pinfunction "D2_N_B7") (pintype "bidirectional"))
    )
    (net (code "57") (name "/USBC_P") (class "Default")
      (node (ref "P3") (pin "3") (pinfunction "3_3") (pintype "passive"))
      (node (ref "P7") (pin "A6") (pinfunction "D1_P_A6") (pintype "bidirectional"))
      (node (ref "P7") (pin "B6") (pinfunction "D2_P_B6") (pintype "bidirectional"))
    )
    (net (code "58") (name "/VBAT_DUT_ISENSE") (class "Default")
      (node (ref "Q1") (pin "2") (pinfunction "D_2") (pintype "passive"))
      (node (ref "Q1") (pin "3") (pinfunction "D_3") (pintype "passive"))
      (node (ref "R3") (pin "1") (pinfunction "1_1") (pintype "passive"))
      (node (ref "U3") (pin "8") (pinfunction "3Y_8") (pintype "passive"))
    )
    (net (code "59") (name "/VBAT_SIM") (class "Default")
      (node (ref "C5") (pin "1") (pinfunction "1_1") (pintype "passive"))
      (node (ref "C6") (pin "1") (pinfunction "1_1") (pintype "passive"))
      (node (ref "D1") (pin "2") (pinfunction "K_2") (pintype "passive"))
      (node (ref "D3") (pin "1") (pinfunction "A_1") (pintype "passive"))
      (node (ref "D5") (pin "1") (pinfunction "A_1") (pintype "passive"))
      (node (ref "L1") (pin "2") (pinfunction "2_2") (pintype "passive"))
      (node (ref "Q1") (pin "4") (pinfunction "S_4") (pintype "passive"))
      (node (ref "R1") (pin "1") (pinfunction "1_1") (pintype "passive"))
      (node (ref "R10") (pin "2") (pinfunction "2_2") (pintype "passive"))
      (node (ref "R13") (pin "1") (pinfunction "1_1") (pintype "passive"))
      (node (ref "R4") (pin "1") (pinfunction "1_1") (pintype "passive"))
      (node (ref "R6") (pin "2") (pinfunction "2_2") (pintype "passive"))
      (node (ref "R7") (pin "1") (pinfunction "1_1") (pintype "passive"))
      (node (ref "U3") (pin "11") (pinfunction "4Y_11") (pintype "passive"))
    )
    (net (code "60") (name "/VBAT_SRC_DUT") (class "Default")
      (node (ref "C7") (pin "2") (pinfunction "2_2") (pintype "passive"))
      (node (ref "D2") (pin "1") (pinfunction "A_1") (pintype "passive"))
      (node (ref "D4") (pin "2") (pinfunction "K_2") (pintype "passive"))
      (node (ref "P1") (pin "1") (pinfunction "1_1") (pintype "passive"))
      (node (ref "R1") (pin "2") (pinfunction "2_2") (pintype "passive"))
      (node (ref "R3") (pin "2") (pinfunction "2_2") (pintype "passive"))
      (node (ref "U5") (pin "4") (pinfunction "VIN-_4") (pintype "input"))
    )
    (net (code "61") (name "/VBUS_DUT") (class "Default")
      (node (ref "C15") (pin "2") (pinfunction "2_2") (pintype "passive"))
      (node (ref "P3") (pin "1") (pinfunction "1_1") (pintype "passive"))
      (node (ref "R24") (pin "1") (pinfunction "1_1") (pintype "passive"))
      (node (ref "R26") (pin "2") (pinfunction "2_2") (pintype "passive"))
      (node (ref "R31") (pin "1") (pinfunction "1_1") (pintype "passive"))
      (node (ref "U8") (pin "4") (pinfunction "VIN-_4") (pintype "input"))
    )
    (net (code "62") (name "/VBUS_EN") (class "Default")
      (node (ref "Q6") (pin "1") (pinfunction "G_1") (pintype "passive"))
      (node (ref "R37") (pin "2") (pinfunction "2_2") (pintype "passive"))
    )
    (net (code "63") (name "/VBUS_SENSE_ADC") (class "Default")
      (node (ref "D7") (pin "2") (pinfunction "A_2") (pintype "passive"))
      (node (ref "R24") (pin "2") (pinfunction "2_2") (pintype "passive"))
      (node (ref "R25") (pin "1") (pinfunction "1_1") (pintype "passive"))
      (node (ref "U4") (pin "12") (pinfunction "IN4_12") (pintype "input"))
    )
    (net (code "64") (name "/VFB5.0") (class "Default")
      (node (ref "C21") (pin "2") (pinfunction "2_2") (pintype "passive"))
      (node (ref "R53") (pin "1") (pinfunction "1_1") (pintype "passive"))
      (node (ref "R57") (pin "2") (pinfunction "2_2") (pintype "passive"))
      (node (ref "U11") (pin "2") (pinfunction "VFB_2") (pintype "input"))
    )
    (net (code "65") (name "/VREG5.0") (class "Default")
      (node (ref "C34") (pin "1") (pinfunction "1_1") (pintype "passive"))
      (node (ref "U11") (pin "3") (pinfunction "VREG5_3") (pintype "power_in"))
    )
    (net (code "66") (name "GND") (class "Default")
      (node (ref "C1") (pin "2") (pinfunction "2_2") (pintype "passive"))
      (node (ref "C10") (pin "2") (pinfunction "2_2") (pintype "passive"))
      (node (ref "C11") (pin "2") (pinfunction "2_2") (pintype "passive"))
      (node (ref "C12") (pin "2") (pinfunction "2_2") (pintype "passive"))
      (node (ref "C14") (pin "2") (pinfunction "2_2") (pintype "passive"))
      (node (ref "C15") (pin "1") (pinfunction "1_1") (pintype "passive"))
      (node (ref "C16") (pin "1") (pinfunction "1_1") (pintype "passive"))
      (node (ref "C17") (pin "1") (pinfunction "1_1") (pintype "passive"))
      (node (ref "C18") (pin "2") (pinfunction "2_2") (pintype "passive"))
      (node (ref "C19") (pin "2") (pinfunction "2_2") (pintype "passive"))
      (node (ref "C2") (pin "2") (pinfunction "2_2") (pintype "passive"))
      (node (ref "C20") (pin "2") (pinfunction "2_2") (pintype "passive"))
      (node (ref "C22") (pin "2") (pinfunction "2_2") (pintype "passive"))
      (node (ref "C23") (pin "1") (pinfunction "1_1") (pintype "passive"))
      (node (ref "C24") (pin "1") (pinfunction "1_1") (pintype "passive"))
      (node (ref "C25") (pin "2") (pinfunction "2_2") (pintype "passive"))
      (node (ref "C26") (pin "2") (pinfunction "2_2") (pintype "passive"))
      (node (ref "C27") (pin "2") (pinfunction "2_2") (pintype "passive"))
      (node (ref "C29") (pin "1") (pinfunction "1_1") (pintype "passive"))
      (node (ref "C3") (pin "2") (pinfunction "2_2") (pintype "passive"))
      (node (ref "C31") (pin "2") (pinfunction "2_2") (pintype "passive"))
      (node (ref "C32") (pin "2") (pinfunction "2_2") (pintype "passive"))
      (node (ref "C33") (pin "2") (pinfunction "2_2") (pintype "passive"))
      (node (ref "C34") (pin "2") (pinfunction "2_2") (pintype "passive"))
      (node (ref "C4") (pin "2") (pinfunction "2_2") (pintype "passive"))
      (node (ref "C5") (pin "2") (pinfunction "2_2") (pintype "passive"))
      (node (ref "C6") (pin "2") (pinfunction "2_2") (pintype "passive"))
      (node (ref "C7") (pin "1") (pinfunction "1_1") (pintype "passive"))
      (node (ref "C8") (pin "2") (pinfunction "2_2") (pintype "passive"))
      (node (ref "C9") (pin "2") (pinfunction "2_2") (pintype "passive"))
      (node (ref "J1") (pin "5") (pinfunction "R_5") (pintype "input"))
      (node (ref "JP1") (pin "2") (pintype "power_in"))
      (node (ref "JP1") (pin "3") (pintype "power_in"))
      (node (ref "P1") (pin "2") (pinfunction "2_2") (pintype "passive"))
      (node (ref "P12") (pin "3") (pinfunction "3_3") (pintype "passive"))
      (node (ref "P3") (pin "0") (pinfunction "0_0") (pintype "passive"))
      (node (ref "P3") (pin "4") (pinfunction "4_4") (pintype "passive"))
      (node (ref "P4") (pin "1") (pinfunction "1_1") (pintype "passive"))
      (node (ref "P6") (pin "2") (pinfunction "2_2") (pintype "passive"))
      (node (ref "P7") (pin "0") (pinfunction "SHELL_0") (pintype "passive"))
      (node (ref "P7") (pin "A1") (pinfunction "GND_A1") (pintype "power_in"))
      (node (ref "P7") (pin "A12") (pinfunction "GND_A12") (pintype "power_in"))
      (node (ref "P7") (pin "B1") (pinfunction "GND_B1") (pintype "power_in"))
      (node (ref "P7") (pin "B12") (pinfunction "GND_B12") (pintype "power_in"))
      (node (ref "Q2") (pin "2") (pinfunction "S_2") (pintype "passive"))
      (node (ref "Q3") (pin "2") (pinfunction "S_2") (pintype "passive"))
      (node (ref "Q6") (pin "2") (pinfunction "S_2") (pintype "passive"))
      (node (ref "R11") (pin "1") (pinfunction "1_1") (pintype "passive"))
      (node (ref "R12") (pin "1") (pinfunction "1_1") (pintype "passive"))
      (node (ref "R16") (pin "2") (pinfunction "2_2") (pintype "passive"))
      (node (ref "R17") (pin "1") (pinfunction "1_1") (pintype "passive"))
      (node (ref "R19") (pin "1") (pinfunction "1_1") (pintype "passive"))
      (node (ref "R20") (pin "1") (pinfunction "1_1") (pintype "passive"))
      (node (ref "R21") (pin "1") (pinfunction "1_1") (pintype "passive"))
      (node (ref "R23") (pin "2") (pinfunction "2_2") (pintype "passive"))
      (node (ref "R25") (pin "2") (pinfunction "2_2") (pintype "passive"))
      (node (ref "R28") (pin "2") (pinfunction "2_2") (pintype "passive"))
      (node (ref "R30") (pin "2") (pinfunction "2_2") (pintype "passive"))
      (node (ref "R31") (pin "2") (pinfunction "2_2") (pintype "passive"))
      (node (ref "R34") (pin "2") (pinfunction "2_2") (pintype "passive"))
      (node (ref "R36") (pin "2") (pinfunction "2_2") (pintype "passive"))
      (node (ref "R37") (pin "1") (pinfunction "1_1") (pintype "passive"))
      (node (ref "R39") (pin "2") (pinfunction "2_2") (pintype "passive"))
      (node (ref "R4") (pin "2") (pinfunction "2_2") (pintype "passive"))
      (node (ref "R41") (pin "2") (pinfunction "2_2") (pintype "passive"))
      (node (ref "R42") (pin "2") (pinfunction "2_2") (pintype "passive"))
      (node (ref "R44") (pin "2") (pinfunction "2_2") (pintype "passive"))
      (node (ref "R46") (pin "2") (pinfunction "2_2") (pintype "passive"))
      (node (ref "R47") (pin "1") (pinfunction "1_1") (pintype "passive"))
      (node (ref "R5") (pin "1") (pinfunction "1_1") (pintype "passive"))
      (node (ref "R50") (pin "2") (pinfunction "2_2") (pintype "passive"))
      (node (ref "R52") (pin "2") (pinfunction "2_2") (pintype "passive"))
      (node (ref "R55") (pin "2") (pinfunction "2_2") (pintype "passive"))
      (node (ref "R57") (pin "1") (pinfunction "1_1") (pintype "passive"))
      (node (ref "R58") (pin "2") (pinfunction "2_2") (pintype "passive"))
      (node (ref "R8") (pin "2") (pinfunction "2_2") (pintype "passive"))
      (node (ref "U1") (pin "4") (pinfunction "GND_4") (pintype "power_in"))
      (node (ref "U1") (pin "7") (pinfunction "A0_7") (pintype "input"))
      (node (ref "U1") (pin "8") (pinfunction "A1_8") (pintype "input"))
      (node (ref "U10") (pin "3") (pinfunction "GND_3") (pintype "power_in"))
      (node (ref "U11") (pin "5") (pinfunction "GND_5") (pintype "power_in"))
      (node (ref "U11") (pin "9") (pinfunction "GND-EP_9") (pintype "power_in"))
      (node (ref "U2") (pin "10") (pinfunction "SGND_10") (pintype "power_in"))
      (node (ref "U2") (pin "11") (pinfunction "NC_11") (pintype "passive"))
      (node (ref "U2") (pin "13") (pinfunction "NC_13") (pintype "passive"))
      (node (ref "U2") (pin "18") (pinfunction "NC_18") (pintype "passive"))
      (node (ref "U2") (pin "21") (pinfunction "EP_21") (pintype "power_in"))
      (node (ref "U2") (pin "8") (pinfunction "DDR_8") (pintype "input"))
      (node (ref "U3") (pin "13") (pinfunction "1E_13") (pintype "input"))
      (node (ref "U3") (pin "5") (pinfunction "2E_5") (pintype "input"))
      (node (ref "U3") (pin "7") (pinfunction "GND_7") (pintype "power_in"))
      (node (ref "U4") (pin "4") (pinfunction "GND_4") (pintype "power_in"))
      (node (ref "U5") (pin "2") (pinfunction "GND_2") (pintype "power_in"))
      (node (ref "U6") (pin "12") (pinfunction "4E_12") (pintype "input"))
      (node (ref "U6") (pin "7") (pinfunction "GND_7") (pintype "power_in"))
      (node (ref "U7") (pin "2") (pinfunction "V-_2") (pintype "power_in"))
      (node (ref "U8") (pin "2") (pinfunction "GND_2") (pintype "power_in"))
      (node (ref "U9") (pin "2") (pinfunction "V-_2") (pintype "power_in"))
    )
    (net (code "67") (name "Net-(D1-A)") (class "Default")
      (node (ref "D1") (pin "1") (pinfunction "A_1") (pintype "passive"))
      (node (ref "D2") (pin "2") (pinfunction "K_2") (pintype "passive"))
    )
    (net (code "68") (name "Net-(D3-K)") (class "Default")
      (node (ref "D3") (pin "2") (pinfunction "K_2") (pintype "passive"))
      (node (ref "D4") (pin "1") (pinfunction "A_1") (pintype "passive"))
    )
    (net (code "69") (name "Net-(D19-K)") (class "Default")
      (node (ref "D19") (pin "2") (pinfunction "K_2") (pintype "passive"))
      (node (ref "R58") (pin "1") (pinfunction "1_1") (pintype "passive"))
    )
    (net (code "70") (name "Net-(L1-Pad1)") (class "Default")
      (node (ref "L1") (pin "1") (pinfunction "1_1") (pintype "passive"))
      (node (ref "U2") (pin "12") (pinfunction "SW_12") (pintype "power_in"))
      (node (ref "U2") (pin "14") (pinfunction "SW_14") (pintype "power_in"))
      (node (ref "U2") (pin "17") (pinfunction "SW_17") (pintype "power_in"))
      (node (ref "U2") (pin "19") (pinfunction "SW_19") (pintype "power_in"))
    )
    (net (code "71") (name "Net-(Q4-D-Pad2)") (class "Default")
      (node (ref "Q4") (pin "2") (pinfunction "D_2") (pintype "passive"))
      (node (ref "Q4") (pin "3") (pinfunction "D_3") (pintype "passive"))
      (node (ref "Q5") (pin "2") (pinfunction "D_2") (pintype "passive"))
      (node (ref "Q5") (pin "3") (pinfunction "D_3") (pintype "passive"))
    )
    (net (code "72") (name "Net-(Q4-G)") (class "Default")
      (node (ref "Q4") (pin "1") (pinfunction "G_1") (pintype "passive"))
      (node (ref "Q5") (pin "1") (pinfunction "G_1") (pintype "passive"))
      (node (ref "Q6") (pin "3") (pinfunction "D_3") (pintype "passive"))
      (node (ref "R32") (pin "1") (pinfunction "1_1") (pintype "passive"))
    )
    (net (code "73") (name "Net-(U1-~{INT})") (class "Default")
      (node (ref "R56") (pin "1") (pinfunction "1_1") (pintype "passive"))
      (node (ref "U1") (pin "6") (pinfunction "~{INT}_6") (pintype "output"))
    )
    (net (code "74") (name "Net-(U3-3Z)") (class "Default")
      (node (ref "U3") (pin "10") (pinfunction "4Z_10") (pintype "passive"))
      (node (ref "U3") (pin "9") (pinfunction "3Z_9") (pintype "passive"))
      (node (ref "U5") (pin "3") (pinfunction "VIN+_3") (pintype "input"))
    )
    (net (code "75") (name "Net-(U4-~{INT})") (class "Default")
      (node (ref "R59") (pin "1") (pinfunction "1_1") (pintype "passive"))
      (node (ref "U4") (pin "6") (pinfunction "~{INT}_6") (pintype "output"))
    )
    (net (code "76") (name "Net-(U6-1Z)") (class "Default")
      (node (ref "R14") (pin "1") (pinfunction "1_1") (pintype "passive"))
      (node (ref "R15") (pin "2") (pinfunction "2_2") (pintype "passive"))
      (node (ref "U6") (pin "10") (pinfunction "4Z_10") (pintype "passive"))
      (node (ref "U6") (pin "2") (pinfunction "1Z_2") (pintype "passive"))
      (node (ref "U6") (pin "3") (pinfunction "2Z_3") (pintype "passive"))
      (node (ref "U6") (pin "9") (pinfunction "3Z_9") (pintype "passive"))
    )
    (net (code "77") (name "Net-(U10-~{FLT})") (class "Default")
      (node (ref "R62") (pin "1") (pinfunction "1_1") (pintype "passive"))
      (node (ref "U10") (pin "8") (pinfunction "~{FLT}_8") (pintype "open_collector"))
    )
    (net (code "78") (name "P3.3VA") (class "Default")
      (node (ref "C1") (pin "1") (pinfunction "1_1") (pintype "passive"))
      (node (ref "C10") (pin "1") (pinfunction "1_1") (pintype "passive"))
      (node (ref "C11") (pin "1") (pinfunction "1_1") (pintype "passive"))
      (node (ref "C12") (pin "1") (pinfunction "1_1") (pintype "passive"))
      (node (ref "C18") (pin "1") (pinfunction "1_1") (pintype "passive"))
      (node (ref "C19") (pin "1") (pinfunction "1_1") (pintype "passive"))
      (node (ref "C2") (pin "1") (pinfunction "1_1") (pintype "passive"))
      (node (ref "C27") (pin "1") (pinfunction "1_1") (pintype "passive"))
      (node (ref "C9") (pin "1") (pinfunction "1_1") (pintype "passive"))
      (node (ref "D10") (pin "1") (pinfunction "K_1") (pintype "passive"))
      (node (ref "D11") (pin "1") (pinfunction "K_1") (pintype "passive"))
      (node (ref "D12") (pin "1") (pinfunction "K_1") (pintype "passive"))
      (node (ref "D13") (pin "1") (pinfunction "K_1") (pintype "passive"))
      (node (ref "D14") (pin "1") (pinfunction "K_1") (pintype "passive"))
      (node (ref "D15") (pin "1") (pinfunction "K_1") (pintype "passive"))
      (node (ref "D16") (pin "1") (pinfunction "K_1") (pintype "passive"))
      (node (ref "D17") (pin "1") (pinfunction "K_1") (pintype "passive"))
      (node (ref "D18") (pin "1") (pinfunction "K_1") (pintype "passive"))
      (node (ref "D6") (pin "1") (pinfunction "K_1") (pintype "passive"))
      (node (ref "D7") (pin "1") (pinfunction "K_1") (pintype "passive"))
      (node (ref "D8") (pin "1") (pinfunction "K_1") (pintype "passive"))
      (node (ref "D9") (pin "1") (pinfunction "K_1") (pintype "passive"))
      (node (ref "R14") (pin "2") (pinfunction "2_2") (pintype "passive"))
      (node (ref "R2") (pin "2") (pinfunction "2_2") (pintype "passive"))
      (node (ref "R62") (pin "2") (pinfunction "2_2") (pintype "passive"))
      (node (ref "U1") (pin "5") (pinfunction "V+_5") (pintype "power_in"))
      (node (ref "U10") (pin "1") (pinfunction "OUT_1") (pintype "power_in"))
      (node (ref "U10") (pin "4") (pinfunction "OUT_4") (pintype "power_in"))
      (node (ref "U4") (pin "5") (pinfunction "V+_5") (pintype "power_in"))
      (node (ref "U4") (pin "7") (pinfunction "A0_7") (pintype "input"))
      (node (ref "U4") (pin "8") (pinfunction "A1_8") (pintype "input"))
      (node (ref "U5") (pin "5") (pinfunction "V+_5") (pintype "power_in"))
      (node (ref "U6") (pin "14") (pinfunction "VCC_14") (pintype "power_in"))
      (node (ref "U7") (pin "5") (pinfunction "V+_5") (pintype "power_in"))
      (node (ref "U8") (pin "5") (pinfunction "V+_5") (pintype "power_in"))
      (node (ref "U9") (pin "5") (pinfunction "V+_5") (pintype "power_in"))
    )
    (net (code "79") (name "P5.0V") (class "Default")
      (node (ref "C16") (pin "2") (pinfunction "2_2") (pintype "passive"))
      (node (ref "C21") (pin "1") (pinfunction "1_1") (pintype "passive"))
      (node (ref "C26") (pin "1") (pinfunction "1_1") (pintype "passive"))
      (node (ref "C3") (pin "1") (pinfunction "1_1") (pintype "passive"))
      (node (ref "C31") (pin "1") (pinfunction "1_1") (pintype "passive"))
      (node (ref "C32") (pin "1") (pinfunction "1_1") (pintype "passive"))
      (node (ref "C4") (pin "1") (pinfunction "1_1") (pintype "passive"))
      (node (ref "C8") (pin "1") (pinfunction "1_1") (pintype "passive"))
      (node (ref "D19") (pin "1") (pinfunction "A_1") (pintype "passive"))
      (node (ref "D5") (pin "2") (pinfunction "K_2") (pintype "passive"))
      (node (ref "L2") (pin "2") (pinfunction "2_2") (pintype "passive"))
      (node (ref "Q4") (pin "4") (pinfunction "S_4") (pintype "passive"))
      (node (ref "R32") (pin "2") (pinfunction "2_2") (pintype "passive"))
      (node (ref "R53") (pin "2") (pinfunction "2_2") (pintype "passive"))
      (node (ref "R9") (pin "2") (pinfunction "2_2") (pintype "passive"))
      (node (ref "U10") (pin "2") (pinfunction "IN_2") (pintype "power_in"))
      (node (ref "U10") (pin "7") (pinfunction "~{SD}_7") (pintype "input"))
      (node (ref "U2") (pin "1") (pinfunction "SVIN_1") (pintype "power_in"))
      (node (ref "U2") (pin "15") (pinfunction "PVIN_15") (pintype "power_in"))
      (node (ref "U2") (pin "16") (pinfunction "PVIN_16") (pintype "power_in"))
      (node (ref "U2") (pin "20") (pinfunction "PVIN_DRV_20") (pintype "power_in"))
      (node (ref "U2") (pin "6") (pinfunction "ITH_6") (pintype "passive"))
      (node (ref "U2") (pin "7") (pinfunction "TRACK/SS_7") (pintype "input"))
      (node (ref "U3") (pin "14") (pinfunction "VCC_14") (pintype "power_in"))
    )
    (net (code "80") (name "P12V") (class "Default")
      (node (ref "C22") (pin "1") (pinfunction "1_1") (pintype "passive"))
      (node (ref "C23") (pin "2") (pinfunction "2_2") (pintype "passive"))
      (node (ref "C24") (pin "2") (pinfunction "2_2") (pintype "passive"))
      (node (ref "C25") (pin "1") (pinfunction "1_1") (pintype "passive"))
      (node (ref "JP1") (pin "1") (pintype "power_in"))
      (node (ref "U11") (pin "1") (pinfunction "EN_1") (pintype "input"))
      (node (ref "U11") (pin "8") (pinfunction "VIN_8") (pintype "power_in"))
    )
    (net (code "81") (name "unconnected-(J1-TN-Pad2)") (class "Default")
      (node (ref "J1") (pin "2") (pinfunction "TN_2") (pintype "passive"))
    )
    (net (code "82") (name "unconnected-(P7-CC2-PadB5)") (class "Default")
      (node (ref "P7") (pin "B5") (pinfunction "CC2_B5") (pintype "bidirectional"))
    )
    (net (code "83") (name "unconnected-(P7-SBU1-PadA8)") (class "Default")
      (node (ref "P7") (pin "A8") (pinfunction "SBU1_A8") (pintype "passive"))
    )
    (net (code "84") (name "unconnected-(P7-SBU2-PadB8)") (class "Default")
      (node (ref "P7") (pin "B8") (pinfunction "SBU2_B8") (pintype "passive+no_connect"))
    )
    (net (code "85") (name "unconnected-(P7-SSRX1_N-PadB10)") (class "Default")
      (node (ref "P7") (pin "B10") (pinfunction "SSRX1_N_B10") (pintype "bidirectional+no_connect"))
    )
    (net (code "86") (name "unconnected-(P7-SSRX1_P-PadB11)") (class "Default")
      (node (ref "P7") (pin "B11") (pinfunction "SSRX1_P_B11") (pintype "bidirectional+no_connect"))
    )
    (net (code "87") (name "unconnected-(P7-SSRX2_N-PadA10)") (class "Default")
      (node (ref "P7") (pin "A10") (pinfunction "SSRX2_N_A10") (pintype "bidirectional+no_connect"))
    )
    (net (code "88") (name "unconnected-(P7-SSRX2_P-PadA11)") (class "Default")
      (node (ref "P7") (pin "A11") (pinfunction "SSRX2_P_A11") (pintype "bidirectional+no_connect"))
    )
    (net (code "89") (name "unconnected-(P7-SSTX1_N-PadA3)") (class "Default")
      (node (ref "P7") (pin "A3") (pinfunction "SSTX1_N_A3") (pintype "bidirectional+no_connect"))
    )
    (net (code "90") (name "unconnected-(P7-SSTX1_P-PadA2)") (class "Default")
      (node (ref "P7") (pin "A2") (pinfunction "SSTX1_P_A2") (pintype "bidirectional+no_connect"))
    )
    (net (code "91") (name "unconnected-(P7-SSTX2_N-PadB3)") (class "Default")
      (node (ref "P7") (pin "B3") (pinfunction "SSTX2_N_B3") (pintype "power_in+no_connect"))
    )
    (net (code "92") (name "unconnected-(P7-SSTX2_P-PadB2)") (class "Default")
      (node (ref "P7") (pin "B2") (pinfunction "SSTX2_P_B2") (pintype "power_in+no_connect"))
    )
    (net (code "93") (name "unconnected-(P7-VBUS-PadA4)") (class "Default")
      (node (ref "P7") (pin "A4") (pinfunction "VBUS_A4") (pintype "power_in"))
    )
    (net (code "94") (name "unconnected-(P7-VBUS-PadA9)") (class "Default")
      (node (ref "P7") (pin "A9") (pinfunction "VBUS_A9") (pintype "power_in"))
    )
    (net (code "95") (name "unconnected-(P7-VBUS-PadB4)") (class "Default")
      (node (ref "P7") (pin "B4") (pinfunction "VBUS_B4") (pintype "power_in"))
    )
    (net (code "96") (name "unconnected-(P7-VBUS-PadB9)") (class "Default")
      (node (ref "P7") (pin "B9") (pinfunction "VBUS_B9") (pintype "power_in"))
    )
    (net (code "97") (name "unconnected-(U1-VREF-Pad1)") (class "Default")
      (node (ref "U1") (pin "1") (pinfunction "VREF_1") (pintype "power_in+no_connect"))
    )
    (net (code "98") (name "unconnected-(U3-1Y-Pad1)") (class "Default")
      (node (ref "U3") (pin "1") (pinfunction "1Y_1") (pintype "passive"))
    )
    (net (code "99") (name "unconnected-(U3-1Z-Pad2)") (class "Default")
      (node (ref "U3") (pin "2") (pinfunction "1Z_2") (pintype "passive"))
    )
    (net (code "100") (name "unconnected-(U3-2Y-Pad4)") (class "Default")
      (node (ref "U3") (pin "4") (pinfunction "2Y_4") (pintype "passive"))
    )
    (net (code "101") (name "unconnected-(U3-2Z-Pad3)") (class "Default")
      (node (ref "U3") (pin "3") (pinfunction "2Z_3") (pintype "passive"))
    )
    (net (code "102") (name "unconnected-(U4-IN5-Pad11)") (class "Default")
      (node (ref "U4") (pin "11") (pinfunction "IN5_11") (pintype "input"))
    )
    (net (code "103") (name "unconnected-(U4-VREF-Pad1)") (class "Default")
      (node (ref "U4") (pin "1") (pinfunction "VREF_1") (pintype "power_in+no_connect"))
    )
    (net (code "104") (name "unconnected-(U6-4Y-Pad11)") (class "Default")
      (node (ref "U6") (pin "11") (pinfunction "4Y_11") (pintype "passive"))
    )
    (net (code "105") (name "unconnected-(U10-NC-Pad5)") (class "Default")
      (node (ref "U10") (pin "5") (pinfunction "NC_5") (pintype "passive"))
    )
  )
)
